# NuTubeAmp_1_0_1.net
KiCad netlist of a schematic drawn in EAGLE
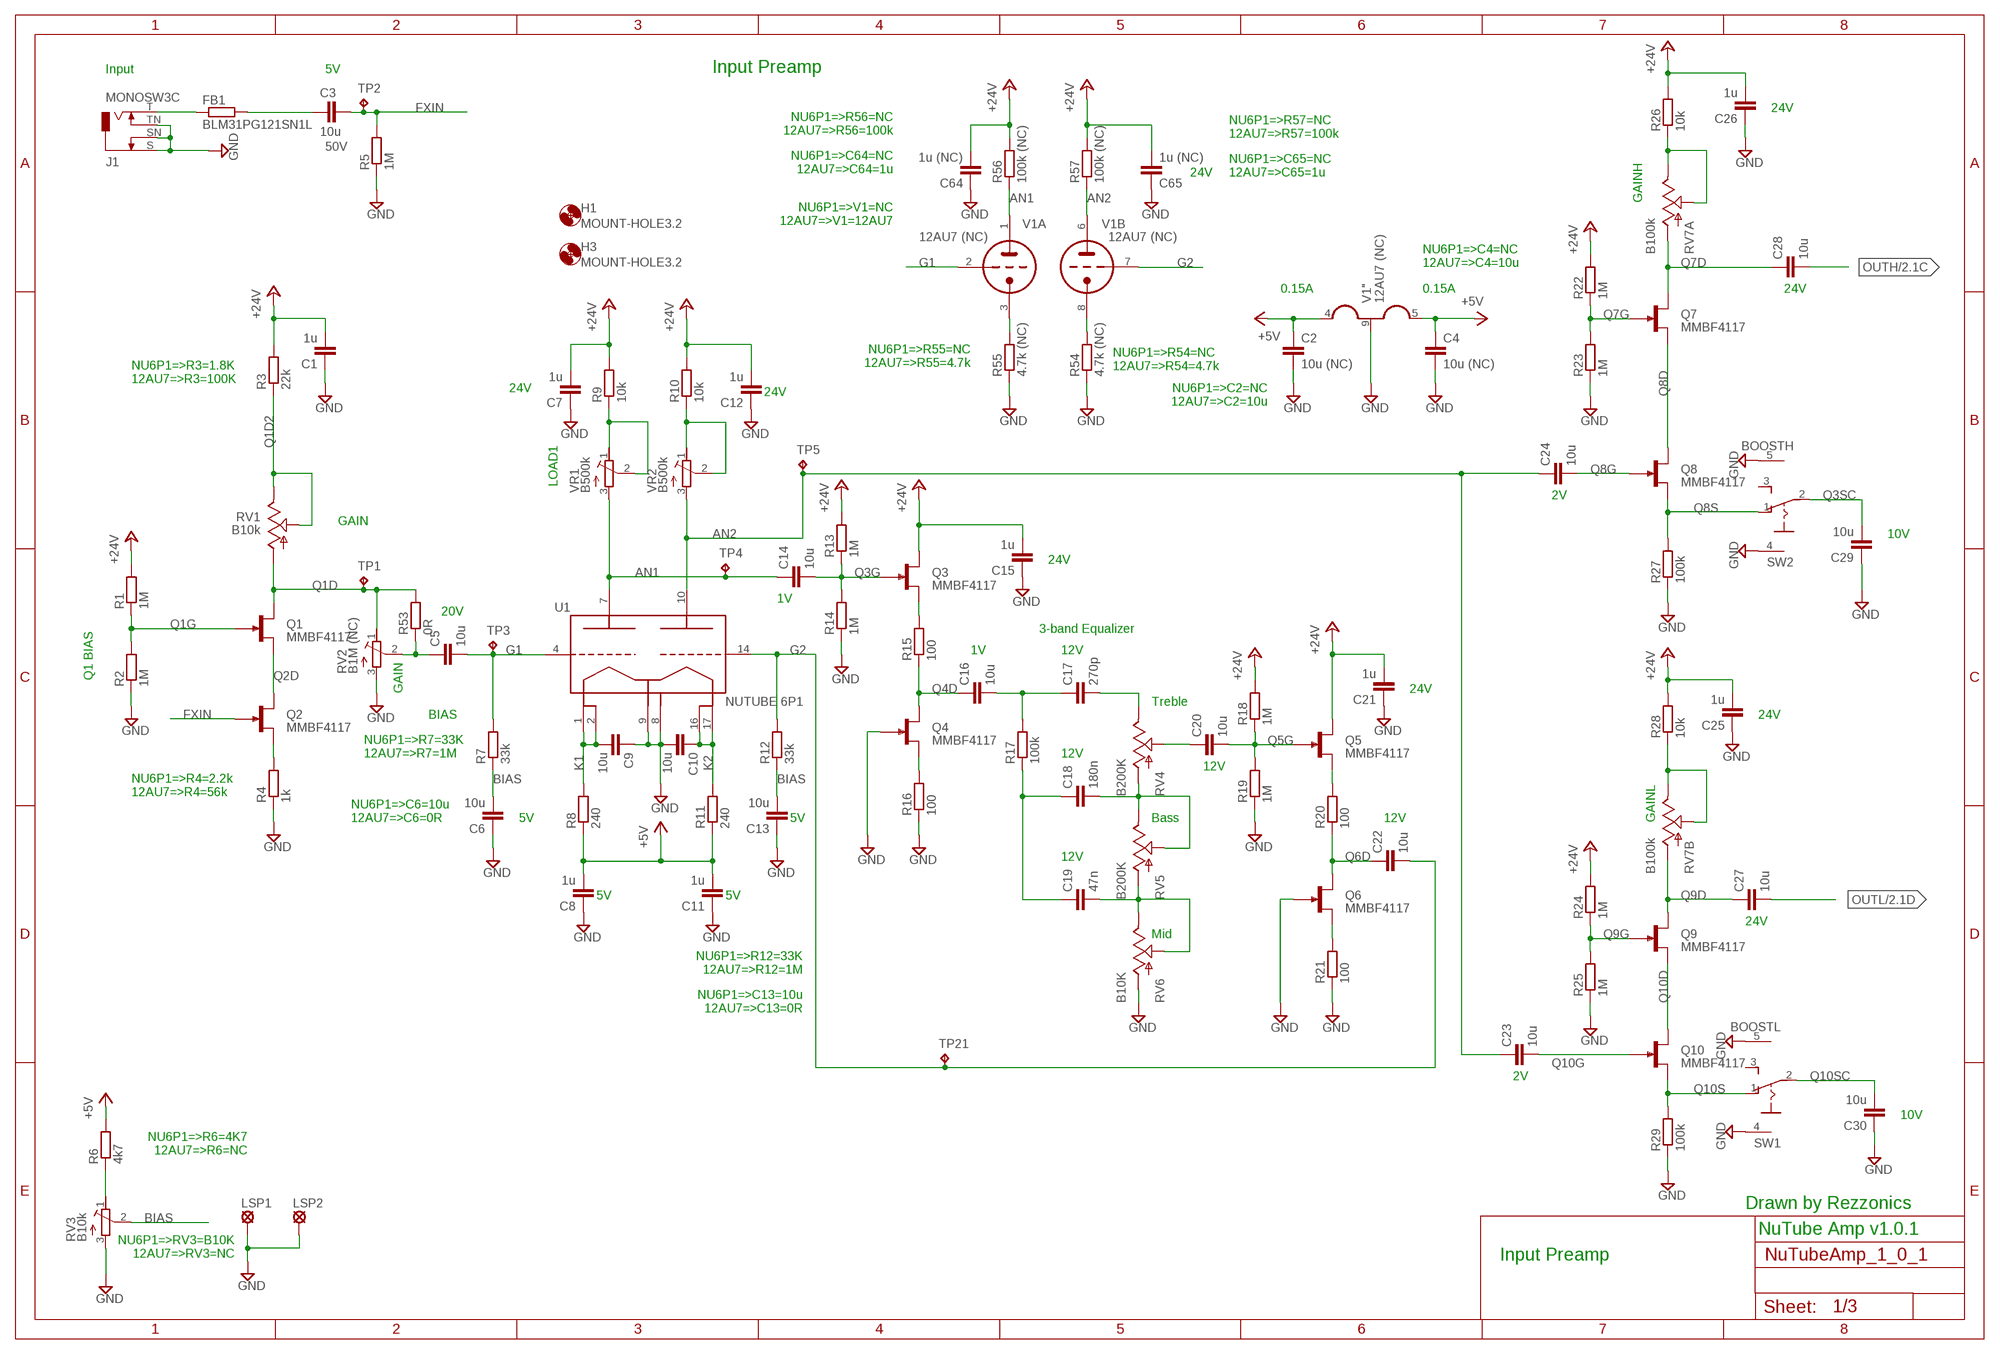
[diagram p0: schematic, sheet 1]
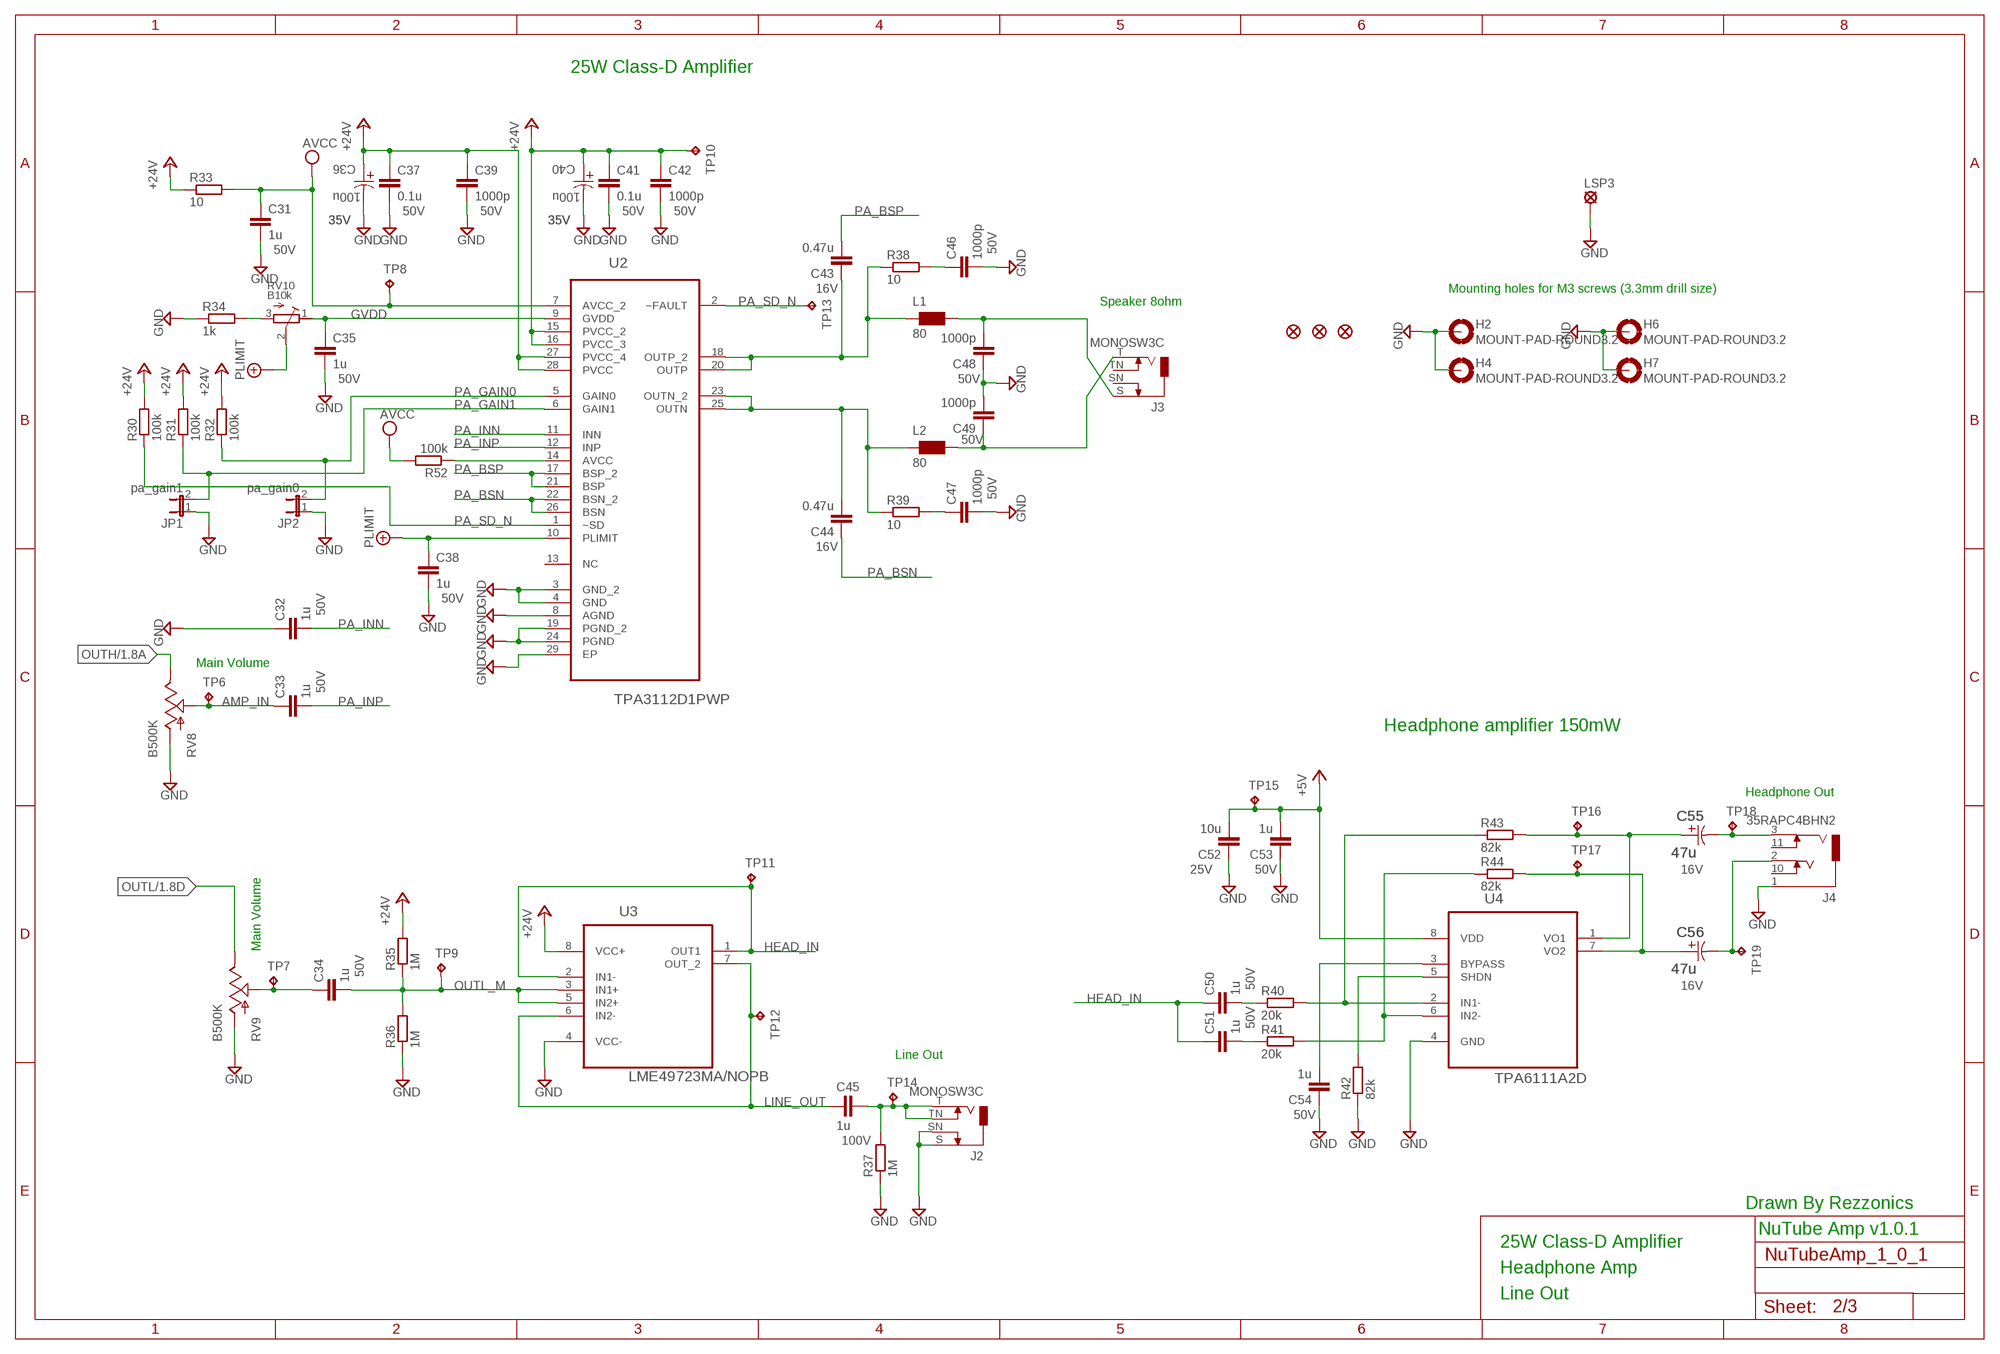
[diagram p1: schematic, sheet 2]
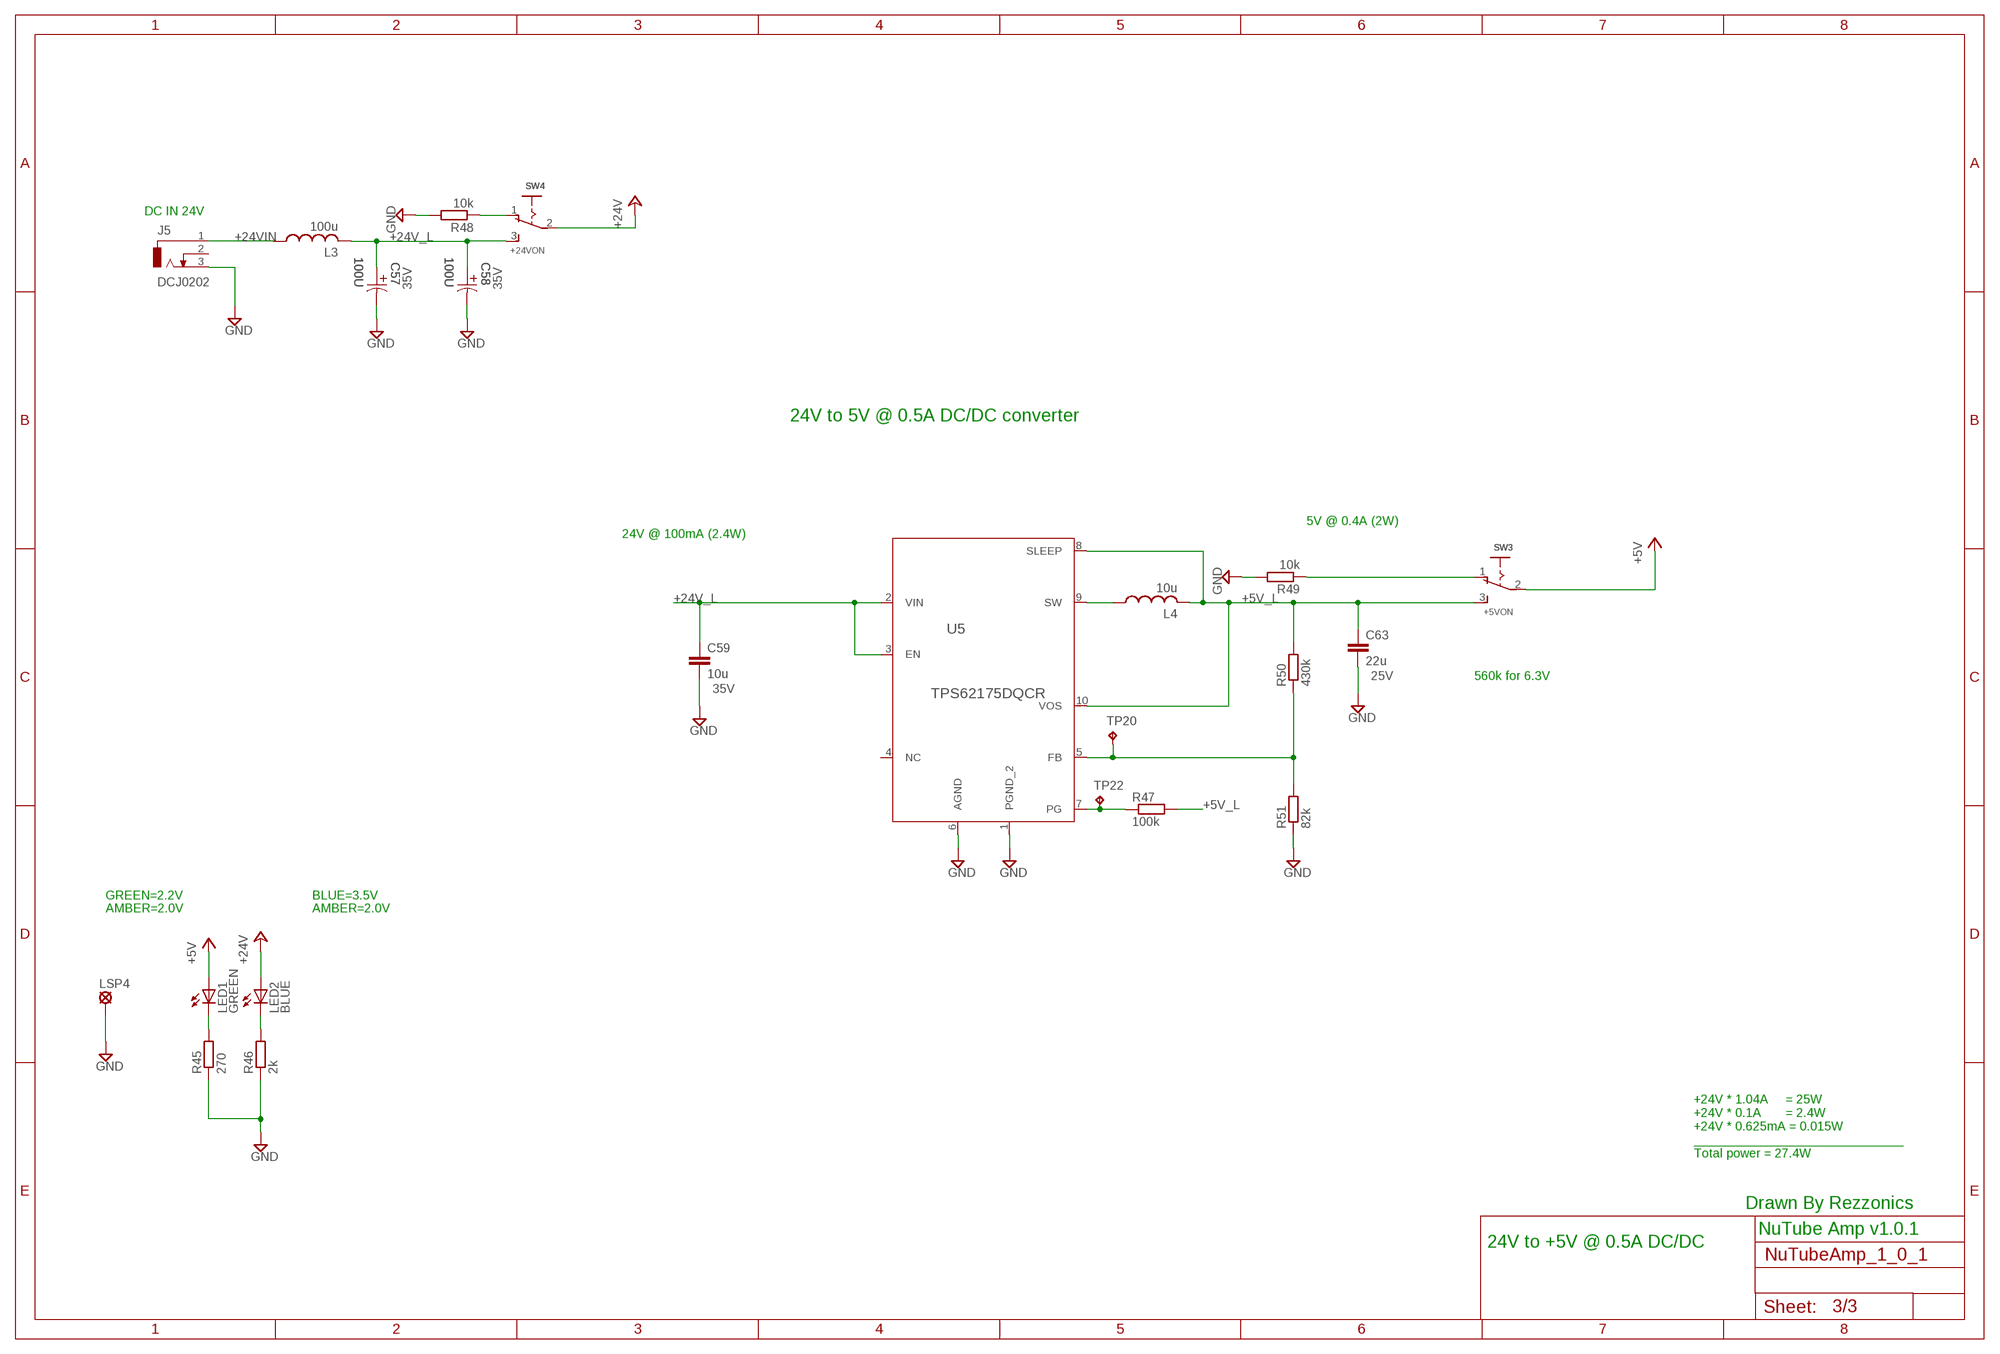
[diagram p2: schematic, sheet 3]

(export (version "E")
  (design (tool "Eeschema 10.0.6"))
  (components
    (comp (ref "C57")
      (value "100U")
      (footprint "eagle-import:CAPAE660X800N")
      (fields
        (field (name "MPN") "EEEHAV101XAP")
        (field (name "TOLERANCE") "±20 %")
        (field (name "VOLTAGERATING") "35V")
        (field (name "MPN_1") "EEE-1VA101XP")
        (field (name "VOLTAGERATING_1") "35V")
      )
      (libsource (lib "eagle-import") (part "EEE--CASE-D8HAV101XAP"))
    )
    (comp (ref "C58")
      (value "100U")
      (footprint "eagle-import:CAPAE660X800N")
      (fields
        (field (name "MPN") "EEEHAV101XAP")
        (field (name "TOLERANCE") "±20 %")
        (field (name "VOLTAGERATING") "35V")
        (field (name "MPN_1") "EEE-1VA101XP")
        (field (name "VOLTAGERATING_1") "35V")
      )
      (libsource (lib "eagle-import") (part "EEE--CASE-D8HAV101XAP"))
    )
    (comp (ref "C59")
      (value "10u")
      (footprint "eagle-import:C0805K")
      (fields (field (name "MPN") "GRM21BR6YA106KE43L") (field (name "VOLT") "35V"))
      (libsource (lib "eagle-import") (part "C-EUC0805K"))
    )
    (comp (ref "C63")
      (value "22u")
      (footprint "eagle-import:C0805K")
      (fields (field (name "MPN") "C2012X5R1V226M125AC") (field (name "VOLT") "25V"))
      (libsource (lib "eagle-import") (part "C-EUC0805K"))
    )
    (comp (ref "J5")
      (value "DCJ0202")
      (footprint "eagle-import:DCJ0202")
      (fields (field (name "MPN") "PJ-202A"))
      (libsource (lib "eagle-import") (part "DCJ0202"))
    )
    (comp (ref "L3")
      (value "100u")
      (footprint "eagle-import:SRN1060")
      (fields (field (name "MPN") "SRN1060-101M"))
      (libsource (lib "eagle-import") (part "SRN1060"))
    )
    (comp (ref "L4")
      (value "10u")
      (footprint "eagle-import:SRN4018")
      (fields (field (name "MPN") "SRN4018-100M"))
      (libsource (lib "eagle-import") (part "SRN4018"))
    )
    (comp (ref "LED1")
      (value "GREEN")
      (footprint "eagle-import:LED5MM")
      (fields (field (name "MPN") "SSL-LX5093GD"))
      (libsource (lib "eagle-import") (part "LED5MM"))
    )
    (comp (ref "LED2")
      (value "BLUE")
      (footprint "eagle-import:LED5MM")
      (fields (field (name "MPN") "SSL-LX5093USBD"))
      (libsource (lib "eagle-import") (part "LED5MM"))
    )
    (comp (ref "LSP4")
      (value "LSP13")
      (footprint "eagle-import:LSP13")
      (fields (field (name "MPN") "1249"))
      (libsource (lib "eagle-import") (part "LSP13"))
    )
    (comp (ref "R45")
      (value "270")
      (footprint "eagle-import:R0603")
      (fields (field (name "MPN") "ERJ-PA3F2700V"))
      (libsource (lib "eagle-import") (part "R-EU_R0603"))
    )
    (comp (ref "R46")
      (value "2k")
      (footprint "eagle-import:R0603")
      (fields (field (name "MPN") "ERJ-PA3F2001V"))
      (libsource (lib "eagle-import") (part "R-EU_R0603"))
    )
    (comp (ref "R47")
      (value "100k")
      (footprint "eagle-import:R0402")
      (fields (field (name "MPN") "ERJ-2RKF1003X"))
      (libsource (lib "eagle-import") (part "resistor_R-EU_R0402"))
    )
    (comp (ref "R48")
      (value "10k")
      (footprint "eagle-import:R0603")
      (fields (field (name "MPN") "CR0603-FX-1002HLF"))
      (libsource (lib "eagle-import") (part "R-EU_R0603"))
    )
    (comp (ref "R49")
      (value "10k")
      (footprint "eagle-import:R0603")
      (fields (field (name "MPN") "CR0603-FX-1002HLF"))
      (libsource (lib "eagle-import") (part "R-EU_R0603"))
    )
    (comp (ref "R50")
      (value "430k")
      (footprint "eagle-import:R0402")
      (fields (field (name "MPN") "ERJ-2GEJ434X"))
      (libsource (lib "eagle-import") (part "resistor_R-EU_R0402"))
    )
    (comp (ref "R51")
      (value "82k")
      (footprint "eagle-import:R0402")
      (fields (field (name "MPN") "ERJ-2RKF8202X"))
      (libsource (lib "eagle-import") (part "resistor_R-EU_R0402"))
    )
    (comp (ref "SW3")
      (value "+5VON")
      (footprint "eagle-import:GH39P0")
      (fields (field (name "MPN") "GH36P010001"))
      (libsource (lib "eagle-import") (part "SPDT1G"))
    )
    (comp (ref "SW4")
      (value "+24VON")
      (footprint "eagle-import:GH39P0")
      (fields (field (name "MPN") "GH36P010001"))
      (libsource (lib "eagle-import") (part "SPDT1G"))
    )
    (comp (ref "TP20")
      (value "TPTP10R")
      (footprint "eagle-import:TP10R")
      (libsource (lib "eagle-import") (part "TPTP10R"))
    )
    (comp (ref "TP22")
      (value "TPTP10R")
      (footprint "eagle-import:TP10R")
      (libsource (lib "eagle-import") (part "TPTP10R"))
    )
    (comp (ref "U5")
      (value "TPS62175DQCR")
      (footprint "eagle-import:R-PWSON-N10")
      (libsource (lib "eagle-import") (part "TPS62175DQCR"))
    )
    (comp (ref "C1")
      (value "1u")
      (footprint "eagle-import:C0603K")
      (fields (field (name "MPN") "C1608X5R1H105K080AB"))
      (libsource (lib "eagle-import") (part "C-EUC0603K"))
    )
    (comp (ref "C2")
      (value "10u (NC)")
      (footprint "eagle-import:C0805K")
      (fields (field (name "MPN") "GRM21BR6YA106KE43L"))
      (libsource (lib "eagle-import") (part "C-EUC0805K"))
    )
    (comp (ref "C3")
      (value "10u")
      (footprint "eagle-import:C0805K")
      (fields (field (name "MPN") "GRM21BR6YA106KE43L") (field (name "VOLT") "50V"))
      (libsource (lib "eagle-import") (part "C-EUC0805K"))
    )
    (comp (ref "C4")
      (value "10u (NC)")
      (footprint "eagle-import:C0805K")
      (fields (field (name "MPN") "GRM21BR6YA106KE43L"))
      (libsource (lib "eagle-import") (part "C-EUC0805K"))
    )
    (comp (ref "C5")
      (value "10u")
      (footprint "eagle-import:C0805K")
      (fields (field (name "MPN") "GRM21BR6YA106KE43L"))
      (libsource (lib "eagle-import") (part "C-EUC0805K"))
    )
    (comp (ref "C6")
      (value "10u")
      (footprint "eagle-import:C0805K")
      (fields (field (name "MPN") "GRM21BR6YA106KE43L"))
      (libsource (lib "eagle-import") (part "C-EUC0805K"))
    )
    (comp (ref "C7")
      (value "1u")
      (footprint "eagle-import:C0603K")
      (fields (field (name "MPN") "C1608X5R1H105K080AB"))
      (libsource (lib "eagle-import") (part "C-EUC0603K"))
    )
    (comp (ref "C8")
      (value "1u")
      (footprint "eagle-import:C0603K")
      (fields (field (name "MPN") "C1608X5R1H105K080AB"))
      (libsource (lib "eagle-import") (part "C-EUC0603K"))
    )
    (comp (ref "C9")
      (value "10u")
      (footprint "eagle-import:C0805K")
      (fields (field (name "MPN") "GRM21BR6YA106KE43L"))
      (libsource (lib "eagle-import") (part "C-EUC0805K"))
    )
    (comp (ref "C10")
      (value "10u")
      (footprint "eagle-import:C0805K")
      (fields (field (name "MPN") "GRM21BR6YA106KE43L"))
      (libsource (lib "eagle-import") (part "C-EUC0805K"))
    )
    (comp (ref "C11")
      (value "1u")
      (footprint "eagle-import:C0603K")
      (fields (field (name "MPN") "C1608X5R1H105K080AB"))
      (libsource (lib "eagle-import") (part "C-EUC0603K"))
    )
    (comp (ref "C12")
      (value "1u")
      (footprint "eagle-import:C0603K")
      (fields (field (name "MPN") "C1608X5R1H105K080AB"))
      (libsource (lib "eagle-import") (part "C-EUC0603K"))
    )
    (comp (ref "C13")
      (value "10u")
      (footprint "eagle-import:C0805K")
      (fields (field (name "MPN") "GRM21BR6YA106KE43L"))
      (libsource (lib "eagle-import") (part "C-EUC0805K"))
    )
    (comp (ref "C14")
      (value "10u")
      (footprint "eagle-import:C0805K")
      (fields (field (name "MPN") "GRM21BR6YA106KE43L"))
      (libsource (lib "eagle-import") (part "C-EUC0805K"))
    )
    (comp (ref "C15")
      (value "1u")
      (footprint "eagle-import:C0603K")
      (fields (field (name "MPN") "C1608X5R1H105K080AB"))
      (libsource (lib "eagle-import") (part "C-EUC0603K"))
    )
    (comp (ref "C16")
      (value "10u")
      (footprint "eagle-import:C0805K")
      (fields (field (name "MPN") "GRM21BR6YA106KE43L"))
      (libsource (lib "eagle-import") (part "C-EUC0805K"))
    )
    (comp (ref "C17")
      (value "270p")
      (footprint "eagle-import:C0402K")
      (fields (field (name "MPN") "GRM1555C1H271JA01D") (field (name "VOLT") "50V"))
      (libsource (lib "eagle-import") (part "C-EUC0402K"))
    )
    (comp (ref "C18")
      (value "180n")
      (footprint "eagle-import:C0603K")
      (fields (field (name "MPN") "GRM188R71C184KA01D") (field (name "VOLT") "16V"))
      (libsource (lib "eagle-import") (part "C-EUC0603K"))
    )
    (comp (ref "C19")
      (value "47n")
      (footprint "eagle-import:C0402K")
      (fields (field (name "MPN") "GRM155R71H473KE14D") (field (name "VOLT") "16V"))
      (libsource (lib "eagle-import") (part "C-EUC0402K"))
    )
    (comp (ref "C20")
      (value "10u")
      (footprint "eagle-import:C0805K")
      (fields (field (name "MPN") "GRM21BR6YA106KE43L"))
      (libsource (lib "eagle-import") (part "C-EUC0805K"))
    )
    (comp (ref "C21")
      (value "1u")
      (footprint "eagle-import:C0603K")
      (fields (field (name "MPN") "C1608X5R1H105K080AB"))
      (libsource (lib "eagle-import") (part "C-EUC0603K"))
    )
    (comp (ref "C22")
      (value "10u")
      (footprint "eagle-import:C0805K")
      (fields (field (name "MPN") "GRM21BR6YA106KE43L"))
      (libsource (lib "eagle-import") (part "C-EUC0805K"))
    )
    (comp (ref "C23")
      (value "10u")
      (footprint "eagle-import:C0805K")
      (fields (field (name "MPN") "GRM21BR6YA106KE43L"))
      (libsource (lib "eagle-import") (part "C-EUC0805K"))
    )
    (comp (ref "C24")
      (value "10u")
      (footprint "eagle-import:C0805K")
      (fields (field (name "MPN") "GRM21BR6YA106KE43L"))
      (libsource (lib "eagle-import") (part "C-EUC0805K"))
    )
    (comp (ref "C25")
      (value "1u")
      (footprint "eagle-import:C0603K")
      (fields (field (name "MPN") "C1608X5R1H105K080AB"))
      (libsource (lib "eagle-import") (part "C-EUC0603K"))
    )
    (comp (ref "C26")
      (value "1u")
      (footprint "eagle-import:C0603K")
      (fields (field (name "MPN") "C1608X5R1H105K080AB"))
      (libsource (lib "eagle-import") (part "C-EUC0603K"))
    )
    (comp (ref "C27")
      (value "10u")
      (footprint "eagle-import:C0805K")
      (fields (field (name "MPN") "GRM21BR6YA106KE43L"))
      (libsource (lib "eagle-import") (part "C-EUC0805K"))
    )
    (comp (ref "C28")
      (value "10u")
      (footprint "eagle-import:C0805K")
      (fields (field (name "MPN") "GRM21BR6YA106KE43L"))
      (libsource (lib "eagle-import") (part "C-EUC0805K"))
    )
    (comp (ref "C29")
      (value "10u")
      (footprint "eagle-import:C0805K")
      (fields (field (name "MPN") "GRM21BR6YA106KE43L"))
      (libsource (lib "eagle-import") (part "C-EUC0805K"))
    )
    (comp (ref "C30")
      (value "10u")
      (footprint "eagle-import:C0805K")
      (fields (field (name "MPN") "GRM21BR6YA106KE43L"))
      (libsource (lib "eagle-import") (part "C-EUC0805K"))
    )
    (comp (ref "C64")
      (value "1u (NC)")
      (footprint "eagle-import:C0603K")
      (fields (field (name "MPN") "C1608X5R1H105K080AB"))
      (libsource (lib "eagle-import") (part "C-EUC0603K"))
    )
    (comp (ref "C65")
      (value "1u (NC)")
      (footprint "eagle-import:C0603K")
      (fields (field (name "MPN") "C1608X5R1H105K080AB"))
      (libsource (lib "eagle-import") (part "C-EUC0603K"))
    )
    (comp (ref "FB1")
      (value "BLM31PG121SN1L")
      (footprint "eagle-import:R1206")
      (libsource (lib "eagle-import") (part "R-EU_R1206"))
    )
    (comp (ref "H1")
      (value "MOUNT-HOLE3.2")
      (footprint "eagle-import:3,2")
      (libsource (lib "eagle-import") (part "MOUNT-HOLE3.2"))
    )
    (comp (ref "H3")
      (value "MOUNT-HOLE3.2")
      (footprint "eagle-import:3,2")
      (libsource (lib "eagle-import") (part "MOUNT-HOLE3.2"))
    )
    (comp (ref "J1")
      (value "MONOSW3C")
      (footprint "eagle-import:NEUTRIK-NMJ4HCD2")
      (fields (field (name "MPN") "NMJ4HCD2"))
      (libsource (lib "eagle-import") (part "MONOSW3C"))
    )
    (comp (ref "LSP1")
      (value "LSP13")
      (footprint "eagle-import:LSP13")
      (fields (field (name "MPN") "1249"))
      (libsource (lib "eagle-import") (part "LSP13"))
    )
    (comp (ref "LSP2")
      (value "LSP13")
      (footprint "eagle-import:LSP13")
      (fields (field (name "MPN") "1249"))
      (libsource (lib "eagle-import") (part "LSP13"))
    )
    (comp (ref "Q1")
      (value "MMBF4117")
      (footprint "eagle-import:SOT23")
      (libsource (lib "eagle-import") (part "MMBF4117SOT23"))
    )
    (comp (ref "Q2")
      (value "MMBF4117")
      (footprint "eagle-import:SOT23")
      (libsource (lib "eagle-import") (part "MMBF4117SOT23"))
    )
    (comp (ref "Q3")
      (value "MMBF4117")
      (footprint "eagle-import:SOT23")
      (libsource (lib "eagle-import") (part "MMBF4117SOT23"))
    )
    (comp (ref "Q4")
      (value "MMBF4117")
      (footprint "eagle-import:SOT23")
      (libsource (lib "eagle-import") (part "MMBF4117SOT23"))
    )
    (comp (ref "Q5")
      (value "MMBF4117")
      (footprint "eagle-import:SOT23")
      (libsource (lib "eagle-import") (part "MMBF4117SOT23"))
    )
    (comp (ref "Q6")
      (value "MMBF4117")
      (footprint "eagle-import:SOT23")
      (libsource (lib "eagle-import") (part "MMBF4117SOT23"))
    )
    (comp (ref "Q7")
      (value "MMBF4117")
      (footprint "eagle-import:SOT23")
      (libsource (lib "eagle-import") (part "MMBF4117SOT23"))
    )
    (comp (ref "Q8")
      (value "MMBF4117")
      (footprint "eagle-import:SOT23")
      (libsource (lib "eagle-import") (part "MMBF4117SOT23"))
    )
    (comp (ref "Q9")
      (value "MMBF4117")
      (footprint "eagle-import:SOT23")
      (libsource (lib "eagle-import") (part "MMBF4117SOT23"))
    )
    (comp (ref "Q10")
      (value "MMBF4117")
      (footprint "eagle-import:SOT23")
      (libsource (lib "eagle-import") (part "MMBF4117SOT23"))
    )
    (comp (ref "R1")
      (value "1M")
      (footprint "eagle-import:R0402")
      (fields (field (name "MPN") "ERJ-2RKF1004X"))
      (libsource (lib "eagle-import") (part "resistor_R-EU_R0402"))
    )
    (comp (ref "R2")
      (value "1M")
      (footprint "eagle-import:R0402")
      (fields (field (name "MPN") "ERJ-2RKF1004X"))
      (libsource (lib "eagle-import") (part "resistor_R-EU_R0402"))
    )
    (comp (ref "R3")
      (value "22k")
      (footprint "eagle-import:R0402")
      (fields (field (name "MPN") "ERJ-2RKF1801X"))
      (libsource (lib "eagle-import") (part "resistor_R-EU_R0402"))
    )
    (comp (ref "R4")
      (value "1k")
      (footprint "eagle-import:R0402")
      (fields (field (name "MPN") "ERJ-2RKF2201X"))
      (libsource (lib "eagle-import") (part "resistor_R-EU_R0402"))
    )
    (comp (ref "R5")
      (value "1M")
      (footprint "eagle-import:R0402")
      (fields (field (name "MPN") "ERJ-2RKF1004X"))
      (libsource (lib "eagle-import") (part "resistor_R-EU_R0402"))
    )
    (comp (ref "R6")
      (value "4k7")
      (footprint "eagle-import:R0402")
      (fields (field (name "MPN") "ERJ-2RKF4701X"))
      (libsource (lib "eagle-import") (part "resistor_R-EU_R0402"))
    )
    (comp (ref "R7")
      (value "33k")
      (footprint "eagle-import:R0402")
      (fields (field (name "MPN") "ERJ-2RKF3302X"))
      (libsource (lib "eagle-import") (part "resistor_R-EU_R0402"))
    )
    (comp (ref "R8")
      (value "240")
      (footprint "eagle-import:R0603")
      (fields (field (name "MPN") "ERJ-3EKF2400V"))
      (libsource (lib "eagle-import") (part "R-EU_R0603"))
    )
    (comp (ref "R9")
      (value "10k")
      (footprint "eagle-import:R0402")
      (fields (field (name "MPN") "ERJ-2RKF1002X"))
      (libsource (lib "eagle-import") (part "resistor_R-EU_R0402"))
    )
    (comp (ref "R10")
      (value "10k")
      (footprint "eagle-import:R0402")
      (fields (field (name "MPN") "ERJ-2RKF1002X"))
      (libsource (lib "eagle-import") (part "resistor_R-EU_R0402"))
    )
    (comp (ref "R11")
      (value "240")
      (footprint "eagle-import:R0603")
      (fields (field (name "MPN") "ERJ-3EKF2400V"))
      (libsource (lib "eagle-import") (part "R-EU_R0603"))
    )
    (comp (ref "R12")
      (value "33k")
      (footprint "eagle-import:R0402")
      (fields (field (name "MPN") "ERJ-2RKF3302X"))
      (libsource (lib "eagle-import") (part "resistor_R-EU_R0402"))
    )
    (comp (ref "R13")
      (value "1M")
      (footprint "eagle-import:R0402")
      (fields (field (name "MPN") "ERJ-2RKF1004X"))
      (libsource (lib "eagle-import") (part "resistor_R-EU_R0402"))
    )
    (comp (ref "R14")
      (value "1M")
      (footprint "eagle-import:R0402")
      (fields (field (name "MPN") "ERJ-2RKF1004X"))
      (libsource (lib "eagle-import") (part "resistor_R-EU_R0402"))
    )
    (comp (ref "R15")
      (value "100")
      (footprint "eagle-import:R0402")
      (fields (field (name "MPN") "ERJ-2RKF1000X"))
      (libsource (lib "eagle-import") (part "resistor_R-EU_R0402"))
    )
    (comp (ref "R16")
      (value "100")
      (footprint "eagle-import:R0402")
      (fields (field (name "MPN") "ERJ-2RKF1000X"))
      (libsource (lib "eagle-import") (part "resistor_R-EU_R0402"))
    )
    (comp (ref "R17")
      (value "100k")
      (footprint "eagle-import:R0402")
      (fields (field (name "MPN") "ERJ-2RKF1003X"))
      (libsource (lib "eagle-import") (part "resistor_R-EU_R0402"))
    )
    (comp (ref "R18")
      (value "1M")
      (footprint "eagle-import:R0402")
      (fields (field (name "MPN") "ERJ-2RKF1004X"))
      (libsource (lib "eagle-import") (part "resistor_R-EU_R0402"))
    )
    (comp (ref "R19")
      (value "1M")
      (footprint "eagle-import:R0402")
      (fields (field (name "MPN") "ERJ-2RKF1004X"))
      (libsource (lib "eagle-import") (part "resistor_R-EU_R0402"))
    )
    (comp (ref "R20")
      (value "100")
      (footprint "eagle-import:R0402")
      (fields (field (name "MPN") "ERJ-2RKF1000X"))
      (libsource (lib "eagle-import") (part "resistor_R-EU_R0402"))
    )
    (comp (ref "R21")
      (value "100")
      (footprint "eagle-import:R0402")
      (fields (field (name "MPN") "ERJ-2RKF1000X"))
      (libsource (lib "eagle-import") (part "resistor_R-EU_R0402"))
    )
    (comp (ref "R22")
      (value "1M")
      (footprint "eagle-import:R0402")
      (fields (field (name "MPN") "ERJ-2RKF1004X"))
      (libsource (lib "eagle-import") (part "resistor_R-EU_R0402"))
    )
    (comp (ref "R23")
      (value "1M")
      (footprint "eagle-import:R0402")
      (fields (field (name "MPN") "ERJ-2RKF1004X"))
      (libsource (lib "eagle-import") (part "resistor_R-EU_R0402"))
    )
    (comp (ref "R24")
      (value "1M")
      (footprint "eagle-import:R0402")
      (fields (field (name "MPN") "ERJ-2RKF1004X"))
      (libsource (lib "eagle-import") (part "resistor_R-EU_R0402"))
    )
    (comp (ref "R25")
      (value "1M")
      (footprint "eagle-import:R0402")
      (fields (field (name "MPN") "ERJ-2RKF1004X"))
      (libsource (lib "eagle-import") (part "resistor_R-EU_R0402"))
    )
    (comp (ref "R26")
      (value "10k")
      (footprint "eagle-import:R0402")
      (fields (field (name "MPN") "ERJ-2RKF1002X"))
      (libsource (lib "eagle-import") (part "resistor_R-EU_R0402"))
    )
    (comp (ref "R27")
      (value "100k")
      (footprint "eagle-import:R0402")
      (fields (field (name "MPN") "ERJ-2RKF1003X"))
      (libsource (lib "eagle-import") (part "resistor_R-EU_R0402"))
    )
    (comp (ref "R28")
      (value "10k")
      (footprint "eagle-import:R0402")
      (fields (field (name "MPN") "ERJ-2RKF1002X"))
      (libsource (lib "eagle-import") (part "resistor_R-EU_R0402"))
    )
    (comp (ref "R29")
      (value "100k")
      (footprint "eagle-import:R0402")
      (fields (field (name "MPN") "ERJ-2RKF1003X"))
      (libsource (lib "eagle-import") (part "resistor_R-EU_R0402"))
    )
    (comp (ref "R53")
      (value "0R")
      (footprint "eagle-import:R0402")
      (fields (field (name "MPN") "ERJ-2GE0R00X"))
      (libsource (lib "eagle-import") (part "resistor_R-EU_R0402"))
    )
    (comp (ref "R54")
      (value "4.7k (NC)")
      (footprint "eagle-import:R0402")
      (fields (field (name "MPN") "ERJ-2RKF4701X"))
      (libsource (lib "eagle-import") (part "resistor_R-EU_R0402"))
    )
    (comp (ref "R55")
      (value "4.7k (NC)")
      (footprint "eagle-import:R0402")
      (fields (field (name "MPN") "ERJ-2RKF4701X"))
      (libsource (lib "eagle-import") (part "resistor_R-EU_R0402"))
    )
    (comp (ref "R56")
      (value "100k (NC)")
      (footprint "eagle-import:R0402")
      (fields (field (name "MPN") "ERJ-2RKF1003X"))
      (libsource (lib "eagle-import") (part "resistor_R-EU_R0402"))
    )
    (comp (ref "R57")
      (value "100k (NC)")
      (footprint "eagle-import:R0402")
      (fields (field (name "MPN") "ERJ-2RKF1003X"))
      (libsource (lib "eagle-import") (part "resistor_R-EU_R0402"))
    )
    (comp (ref "RV1")
      (value "B10k")
      (footprint "eagle-import:3310Y")
      (fields (field (name "MPN") "3310Y-001-103L"))
      (libsource (lib "eagle-import") (part "POT3310Y"))
    )
    (comp (ref "RV2")
      (value "B1M (NC)")
      (footprint "eagle-import:RTRIM3314G")
      (fields (field (name "MPN") "3314G-1-105E"))
      (libsource (lib "eagle-import") (part "R-TRIMM3314G"))
    )
    (comp (ref "RV3")
      (value "B10k")
      (footprint "eagle-import:RTRIM3314G")
      (fields (field (name "MPN") "3314G-2-103E"))
      (libsource (lib "eagle-import") (part "R-TRIMM3314G"))
    )
    (comp (ref "RV4")
      (value "B200K")
      (footprint "eagle-import:3310Y")
      (fields (field (name "MPN") "3310Y-001-204L"))
      (libsource (lib "eagle-import") (part "POT3310Y"))
    )
    (comp (ref "RV5")
      (value "B200K")
      (footprint "eagle-import:3310Y")
      (fields (field (name "MPN") "3310Y-001-204L"))
      (libsource (lib "eagle-import") (part "POT3310Y"))
    )
    (comp (ref "RV6")
      (value "B10K")
      (footprint "eagle-import:3310Y")
      (fields (field (name "MPN") "3310Y-001-103L"))
      (libsource (lib "eagle-import") (part "POT3310Y"))
    )
    (comp (ref "RV7")
      (value "B100k")
      (footprint "eagle-import:3310H")
      (fields (field (name "MPN") "3310H-001-104L"))
      (libsource (lib "eagle-import") (part "DPOT1"))
    )
    (comp (ref "SW1")
      (value "BOOSTL")
      (footprint "eagle-import:MHS122K")
      (fields (field (name "MPN") "MHS122K"))
      (libsource (lib "eagle-import") (part "SPDT"))
    )
    (comp (ref "SW2")
      (value "BOOSTH")
      (footprint "eagle-import:MHS122K")
      (fields (field (name "MPN") "MHS122K"))
      (libsource (lib "eagle-import") (part "SPDT"))
    )
    (comp (ref "TP1")
      (value "TPTP10R")
      (footprint "eagle-import:TP10R")
      (libsource (lib "eagle-import") (part "TPTP10R"))
    )
    (comp (ref "TP2")
      (value "TPTP10R")
      (footprint "eagle-import:TP10R")
      (libsource (lib "eagle-import") (part "TPTP10R"))
    )
    (comp (ref "TP3")
      (value "TPTP10R")
      (footprint "eagle-import:TP10R")
      (libsource (lib "eagle-import") (part "TPTP10R"))
    )
    (comp (ref "TP4")
      (value "TPTP10R")
      (footprint "eagle-import:TP10R")
      (libsource (lib "eagle-import") (part "TPTP10R"))
    )
    (comp (ref "TP5")
      (value "TPTP10R")
      (footprint "eagle-import:TP10R")
      (libsource (lib "eagle-import") (part "TPTP10R"))
    )
    (comp (ref "TP21")
      (value "TPTP10R")
      (footprint "eagle-import:TP10R")
      (libsource (lib "eagle-import") (part "TPTP10R"))
    )
    (comp (ref "U1")
      (value "NUTUBE 6P1")
      (footprint "eagle-import:NUTUBE_6P1_1")
      (libsource (lib "eagle-import") (part "NUTUBE_6P1_1"))
    )
    (comp (ref "V1")
      (value "12AU7 (NC)")
      (footprint "eagle-import:VT9")
      (fields (field (name "MPN") "*"))
      (libsource (lib "eagle-import") (part "12AU7-PVT9"))
    )
    (comp (ref "VR1")
      (value "B500k")
      (footprint "eagle-import:RTRIM3314G")
      (fields (field (name "MPN") "3314G-1-504E"))
      (libsource (lib "eagle-import") (part "R-TRIMM3314G"))
    )
    (comp (ref "VR2")
      (value "B500k")
      (footprint "eagle-import:RTRIM3314G")
      (fields (field (name "MPN") "3314G-1-504E"))
      (libsource (lib "eagle-import") (part "R-TRIMM3314G"))
    )
    (comp (ref "C31")
      (value "1u")
      (footprint "eagle-import:C0603K")
      (fields (field (name "MPN") "C1608X5R1H105K080AB") (field (name "VOLT") "50V"))
      (libsource (lib "eagle-import") (part "C-EUC0603K"))
    )
    (comp (ref "C32")
      (value "1u")
      (footprint "eagle-import:C0603K")
      (fields (field (name "MPN") "C1608X5R1H105K080AB") (field (name "VOLT") "50V"))
      (libsource (lib "eagle-import") (part "C-EUC0603K"))
    )
    (comp (ref "C33")
      (value "1u")
      (footprint "eagle-import:C0603K")
      (fields (field (name "MPN") "C1608X5R1H105K080AB") (field (name "VOLT") "50V"))
      (libsource (lib "eagle-import") (part "C-EUC0603K"))
    )
    (comp (ref "C34")
      (value "1u")
      (footprint "eagle-import:C0603K")
      (fields (field (name "MPN") "C1608X5R1H105K080AB") (field (name "VOLT") "50V"))
      (libsource (lib "eagle-import") (part "C-EUC0603K"))
    )
    (comp (ref "C35")
      (value "1u")
      (footprint "eagle-import:C0603K")
      (fields (field (name "MPN") "C1608X5R1H105K080AB") (field (name "VOLT") "50V"))
      (libsource (lib "eagle-import") (part "C-EUC0603K"))
    )
    (comp (ref "C36")
      (value "100u")
      (footprint "eagle-import:CAPAE660X800N")
      (fields
        (field (name "MPN") "EEEHAE101XAP")
        (field (name "TOLERANCE") "±20 %")
        (field (name "VOLTAGERATING") "25V")
        (field (name "MPN_1") "EEE-1VA101XP")
        (field (name "VOLT") "35V")
        (field (name "VOLTAGERATING_1") "35V")
      )
      (libsource (lib "eagle-import") (part "EEE--CASE-D8HAE101XAP"))
    )
    (comp (ref "C37")
      (value "0.1u")
      (footprint "eagle-import:C0603K")
      (fields (field (name "MPN") "GRM188R71H104KA93D") (field (name "VOLT") "50V"))
      (libsource (lib "eagle-import") (part "C-EUC0603K"))
    )
    (comp (ref "C38")
      (value "1u")
      (footprint "eagle-import:C0603K")
      (fields (field (name "MPN") "C1608X5R1H105K080AB") (field (name "VOLT") "50V"))
      (libsource (lib "eagle-import") (part "C-EUC0603K"))
    )
    (comp (ref "C39")
      (value "1000p")
      (footprint "eagle-import:C0603K")
      (fields (field (name "MPN") "GRM1885C1H102FA01D") (field (name "VOLT") "50V"))
      (libsource (lib "eagle-import") (part "C-EUC0603K"))
    )
    (comp (ref "C40")
      (value "100u")
      (footprint "eagle-import:CAPAE660X800N")
      (fields
        (field (name "MPN") "EEEHAE101XAP")
        (field (name "TOLERANCE") "±20 %")
        (field (name "VOLTAGERATING") "25V")
        (field (name "MPN_1") "EEE-1VA101XP")
        (field (name "VOLT") "35V")
        (field (name "VOLTAGERATING_1") "35V")
      )
      (libsource (lib "eagle-import") (part "EEE--CASE-D8HAE101XAP"))
    )
    (comp (ref "C41")
      (value "0.1u")
      (footprint "eagle-import:C0603K")
      (fields (field (name "MPN") "GRM188R71H104KA93D") (field (name "VOLT") "50V"))
      (libsource (lib "eagle-import") (part "C-EUC0603K"))
    )
    (comp (ref "C42")
      (value "1000p")
      (footprint "eagle-import:C0603K")
      (fields (field (name "MPN") "GRM1885C1H102FA01D") (field (name "VOLT") "50V"))
      (libsource (lib "eagle-import") (part "C-EUC0603K"))
    )
    (comp (ref "C43")
      (value "0.47u")
      (footprint "eagle-import:C0603K")
      (fields (field (name "MPN") "GRM188R71C474KA88D") (field (name "VOLT") "16V"))
      (libsource (lib "eagle-import") (part "C-EUC0603K"))
    )
    (comp (ref "C44")
      (value "0.47u")
      (footprint "eagle-import:C0603K")
      (fields (field (name "MPN") "GRM188R71C474KA88D") (field (name "VOLT") "16V"))
      (libsource (lib "eagle-import") (part "C-EUC0603K"))
    )
    (comp (ref "C45")
      (value "1u")
      (footprint "eagle-import:C0603K")
      (fields (field (name "MPN") "C1608X5R1H105K080AB") (field (name "VOLT") "100V"))
      (libsource (lib "eagle-import") (part "C-EUC0603K"))
    )
    (comp (ref "C46")
      (value "1000p")
      (footprint "eagle-import:C0603K")
      (fields (field (name "MPN") "GRM1885C1H102FA01D") (field (name "VOLT") "50V"))
      (libsource (lib "eagle-import") (part "C-EUC0603K"))
    )
    (comp (ref "C47")
      (value "1000p")
      (footprint "eagle-import:C0603K")
      (fields (field (name "MPN") "GRM1885C1H102FA01D") (field (name "VOLT") "50V"))
      (libsource (lib "eagle-import") (part "C-EUC0603K"))
    )
    (comp (ref "C48")
      (value "1000p")
      (footprint "eagle-import:C0603K")
      (fields (field (name "MPN") "GRM1885C1H102FA01D") (field (name "VOLT") "50V"))
      (libsource (lib "eagle-import") (part "C-EUC0603K"))
    )
    (comp (ref "C49")
      (value "1000p")
      (footprint "eagle-import:C0603K")
      (fields (field (name "MPN") "GRM1885C1H102FA01D") (field (name "VOLT") "50V"))
      (libsource (lib "eagle-import") (part "C-EUC0603K"))
    )
    (comp (ref "C50")
      (value "1u")
      (footprint "eagle-import:C0603K")
      (fields (field (name "MPN") "C1608X5R1H105K080AB") (field (name "VOLT") "50V"))
      (libsource (lib "eagle-import") (part "C-EUC0603K"))
    )
    (comp (ref "C51")
      (value "1u")
      (footprint "eagle-import:C0603K")
      (fields (field (name "MPN") "C1608X5R1H105K080AB") (field (name "VOLT") "50V"))
      (libsource (lib "eagle-import") (part "C-EUC0603K"))
    )
    (comp (ref "C52")
      (value "10u")
      (footprint "eagle-import:C0805K")
      (fields (field (name "MPN") "GRM21BR6YA106KE43L") (field (name "VOLT") "25V"))
      (libsource (lib "eagle-import") (part "C-EUC0805K"))
    )
    (comp (ref "C53")
      (value "1u")
      (footprint "eagle-import:C0603K")
      (fields (field (name "MPN") "C1608X5R1H105K080AB") (field (name "VOLT") "50V"))
      (libsource (lib "eagle-import") (part "C-EUC0603K"))
    )
    (comp (ref "C54")
      (value "1u")
      (footprint "eagle-import:C0603K")
      (fields (field (name "MPN") "C1608X5R1H105K080AB") (field (name "VOLT") "50V"))
      (libsource (lib "eagle-import") (part "C-EUC0603K"))
    )
    (comp (ref "C55")
      (value "47u")
      (footprint "eagle-import:CAPAE530X610N")
      (fields
        (field (name "MPN") "EEEHBC470UAR")
        (field (name "TOLERANCE") "±20 %")
        (field (name "MPN_1") "EEE-HBC470UAR")
        (field (name "VOLT") "16V")
      )
      (libsource (lib "eagle-import") (part "EEE--CASE-CHBC470UAR"))
    )
    (comp (ref "C56")
      (value "47u")
      (footprint "eagle-import:CAPAE530X610N")
      (fields
        (field (name "MPN") "EEEHBC470UAR")
        (field (name "TOLERANCE") "±20 %")
        (field (name "MPN_1") "EEE-HBC470UAR")
        (field (name "VOLT") "16V")
      )
      (libsource (lib "eagle-import") (part "EEE--CASE-CHBC470UAR"))
    )
    (comp (ref "H2")
      (value "MOUNT-PAD-ROUND3.2")
      (footprint "eagle-import:3,2-PAD")
      (libsource (lib "eagle-import") (part "MOUNT-PAD-ROUND3.2"))
    )
    (comp (ref "H4")
      (value "MOUNT-PAD-ROUND3.2")
      (footprint "eagle-import:3,2-PAD")
      (libsource (lib "eagle-import") (part "MOUNT-PAD-ROUND3.2"))
    )
    (comp (ref "H6")
      (value "MOUNT-PAD-ROUND3.2")
      (footprint "eagle-import:3,2-PAD")
      (libsource (lib "eagle-import") (part "MOUNT-PAD-ROUND3.2"))
    )
    (comp (ref "H7")
      (value "MOUNT-PAD-ROUND3.2")
      (footprint "eagle-import:3,2-PAD")
      (libsource (lib "eagle-import") (part "MOUNT-PAD-ROUND3.2"))
    )
    (comp (ref "J2")
      (value "MONOSW3C")
      (footprint "eagle-import:NEUTRIK-NMJ4HCD2")
      (fields (field (name "MPN") "NMJ4HCD2"))
      (libsource (lib "eagle-import") (part "MONOSW3C"))
    )
    (comp (ref "J3")
      (value "MONOSW3C")
      (footprint "eagle-import:NEUTRIK-NMJ4HCD2")
      (fields (field (name "MPN") "NMJ4HCD2"))
      (libsource (lib "eagle-import") (part "MONOSW3C"))
    )
    (comp (ref "J4")
      (value "35RAPC4BHN2")
      (footprint "eagle-import:35RAPC4BHN2")
      (libsource (lib "eagle-import") (part "35RAPC4BHN2"))
    )
    (comp (ref "JP1")
      (value "pa_gain1")
      (footprint "eagle-import:1X02")
      (fields (field (name "MPN") "77311-401-36LF"))
      (libsource (lib "eagle-import") (part "JUMPER-2PTH"))
    )
    (comp (ref "JP2")
      (value "pa_gain0")
      (footprint "eagle-import:1X02")
      (fields (field (name "MPN") "77311-401-36LF"))
      (libsource (lib "eagle-import") (part "JUMPER-2PTH"))
    )
    (comp (ref "JP3")
      (value "FIDUCIAL1X2.5")
      (footprint "eagle-import:FIDUCIAL-1X2.5")
      (libsource (lib "eagle-import") (part "FIDUCIAL1X2.5"))
    )
    (comp (ref "JP4")
      (value "FIDUCIAL1X2.5")
      (footprint "eagle-import:FIDUCIAL-1X2.5")
      (libsource (lib "eagle-import") (part "FIDUCIAL1X2.5"))
    )
    (comp (ref "JP5")
      (value "FIDUCIAL1X2.5")
      (footprint "eagle-import:FIDUCIAL-1X2.5")
      (libsource (lib "eagle-import") (part "FIDUCIAL1X2.5"))
    )
    (comp (ref "L1")
      (value "80")
      (footprint "eagle-import:0805")
      (fields (field (name "MPN") "HI0805R800R-10"))
      (libsource (lib "eagle-import") (part "WE-CBF_0805"))
    )
    (comp (ref "L2")
      (value "80")
      (footprint "eagle-import:0805")
      (fields (field (name "MPN") "HI0805R800R-10"))
      (libsource (lib "eagle-import") (part "WE-CBF_0805"))
    )
    (comp (ref "LSP3")
      (value "LSP13")
      (footprint "eagle-import:LSP13")
      (fields (field (name "MPN") "1249"))
      (libsource (lib "eagle-import") (part "LSP13"))
    )
    (comp (ref "R30")
      (value "100k")
      (footprint "eagle-import:R0603")
      (fields (field (name "MPN") "ERJ-3EKF1003V"))
      (libsource (lib "eagle-import") (part "R-EU_R0603"))
    )
    (comp (ref "R31")
      (value "100k")
      (footprint "eagle-import:R0603")
      (fields (field (name "MPN") "ERJ-3EKF1003V"))
      (libsource (lib "eagle-import") (part "R-EU_R0603"))
    )
    (comp (ref "R32")
      (value "100k")
      (footprint "eagle-import:R0603")
      (fields (field (name "MPN") "ERJ-3EKF1003V"))
      (libsource (lib "eagle-import") (part "R-EU_R0603"))
    )
    (comp (ref "R33")
      (value "10")
      (footprint "eagle-import:R0603")
      (fields (field (name "MPN") "CRCW060310R0FKEAHP"))
      (libsource (lib "eagle-import") (part "R-EU_R0603"))
    )
    (comp (ref "R34")
      (value "1k")
      (footprint "eagle-import:R0603")
      (fields (field (name "MPN") "ERJ-3EKF1001V"))
      (libsource (lib "eagle-import") (part "R-EU_R0603"))
    )
    (comp (ref "R35")
      (value "1M")
      (footprint "eagle-import:R0402")
      (fields (field (name "MPN") "ERJ-2RKF1004X"))
      (libsource (lib "eagle-import") (part "resistor_R-EU_R0402"))
    )
    (comp (ref "R36")
      (value "1M")
      (footprint "eagle-import:R0402")
      (fields (field (name "MPN") "ERJ-2RKF1004X"))
      (libsource (lib "eagle-import") (part "resistor_R-EU_R0402"))
    )
    (comp (ref "R37")
      (value "1M")
      (footprint "eagle-import:R0402")
      (fields (field (name "MPN") "ERJ-2RKF1004X"))
      (libsource (lib "eagle-import") (part "resistor_R-EU_R0402"))
    )
    (comp (ref "R38")
      (value "10")
      (footprint "eagle-import:R0603")
      (fields (field (name "MPN") "CRCW060310R0FKEAHP"))
      (libsource (lib "eagle-import") (part "R-EU_R0603"))
    )
    (comp (ref "R39")
      (value "10")
      (footprint "eagle-import:R0603")
      (fields (field (name "MPN") "CRCW060310R0FKEAHP"))
      (libsource (lib "eagle-import") (part "R-EU_R0603"))
    )
    (comp (ref "R40")
      (value "20k")
      (footprint "eagle-import:R0603")
      (fields (field (name "MPN") "ERJ-3EKF2002V"))
      (libsource (lib "eagle-import") (part "resistor_R-EU_R0603"))
    )
    (comp (ref "R41")
      (value "20k")
      (footprint "eagle-import:R0603")
      (fields (field (name "MPN") "ERJ-3EKF2002V"))
      (libsource (lib "eagle-import") (part "resistor_R-EU_R0603"))
    )
    (comp (ref "R42")
      (value "82k")
      (footprint "eagle-import:R0603")
      (fields (field (name "MPN") "ERJ-3EKF8202V"))
      (libsource (lib "eagle-import") (part "resistor_R-EU_R0603"))
    )
    (comp (ref "R43")
      (value "82k")
      (footprint "eagle-import:R0603")
      (fields (field (name "MPN") "ERJ-3EKF8202V"))
      (libsource (lib "eagle-import") (part "resistor_R-EU_R0603"))
    )
    (comp (ref "R44")
      (value "82k")
      (footprint "eagle-import:R0603")
      (fields (field (name "MPN") "ERJ-3EKF8202V"))
      (libsource (lib "eagle-import") (part "resistor_R-EU_R0603"))
    )
    (comp (ref "R52")
      (value "100k")
      (footprint "eagle-import:R0603")
      (fields (field (name "MPN") "ERJ-3EKF1003V"))
      (libsource (lib "eagle-import") (part "R-EU_R0603"))
    )
    (comp (ref "RV8")
      (value "B500K")
      (footprint "eagle-import:3310Y")
      (fields (field (name "MPN") "3310Y-001-504L"))
      (libsource (lib "eagle-import") (part "POT3310Y"))
    )
    (comp (ref "RV9")
      (value "B500K")
      (footprint "eagle-import:3310Y")
      (fields (field (name "MPN") "3310Y-001-504L"))
      (libsource (lib "eagle-import") (part "POT3310Y"))
    )
    (comp (ref "RV10")
      (value "B10k")
      (footprint "eagle-import:RTRIM3314G")
      (fields (field (name "MPN") "3314G-2-103E"))
      (libsource (lib "eagle-import") (part "R-TRIMM3314G"))
    )
    (comp (ref "TP6")
      (value "TPTP10R")
      (footprint "eagle-import:TP10R")
      (libsource (lib "eagle-import") (part "TPTP10R"))
    )
    (comp (ref "TP7")
      (value "TPTP10R")
      (footprint "eagle-import:TP10R")
      (libsource (lib "eagle-import") (part "TPTP10R"))
    )
    (comp (ref "TP8")
      (value "TPTP10R")
      (footprint "eagle-import:TP10R")
      (libsource (lib "eagle-import") (part "TPTP10R"))
    )
    (comp (ref "TP9")
      (value "TPTP10R")
      (footprint "eagle-import:TP10R")
      (libsource (lib "eagle-import") (part "TPTP10R"))
    )
    (comp (ref "TP10")
      (value "TPTP10R")
      (footprint "eagle-import:TP10R")
      (libsource (lib "eagle-import") (part "TPTP10R"))
    )
    (comp (ref "TP11")
      (value "TPTP10R")
      (footprint "eagle-import:TP10R")
      (libsource (lib "eagle-import") (part "TPTP10R"))
    )
    (comp (ref "TP12")
      (value "TPTP10R")
      (footprint "eagle-import:TP10R")
      (libsource (lib "eagle-import") (part "TPTP10R"))
    )
    (comp (ref "TP13")
      (value "TPTP10R")
      (footprint "eagle-import:TP10R")
      (libsource (lib "eagle-import") (part "TPTP10R"))
    )
    (comp (ref "TP14")
      (value "TPTP10R")
      (footprint "eagle-import:TP10R")
      (libsource (lib "eagle-import") (part "TPTP10R"))
    )
    (comp (ref "TP15")
      (value "TPTP10R")
      (footprint "eagle-import:TP10R")
      (libsource (lib "eagle-import") (part "TPTP10R"))
    )
    (comp (ref "TP16")
      (value "TPTP10R")
      (footprint "eagle-import:TP10R")
      (libsource (lib "eagle-import") (part "TPTP10R"))
    )
    (comp (ref "TP17")
      (value "TPTP10R")
      (footprint "eagle-import:TP10R")
      (libsource (lib "eagle-import") (part "TPTP10R"))
    )
    (comp (ref "TP18")
      (value "TPTP10R")
      (footprint "eagle-import:TP10R")
      (libsource (lib "eagle-import") (part "TPTP10R"))
    )
    (comp (ref "TP19")
      (value "TPTP10R")
      (footprint "eagle-import:TP10R")
      (libsource (lib "eagle-import") (part "TPTP10R"))
    )
    (comp (ref "U2")
      (value "TPA3112D1PWP")
      (footprint "eagle-import:SOP65P640X120-29N")
      (fields (field (name "MPN") "TPA3112D1PWP"))
      (libsource (lib "eagle-import") (part "TPA3112D1PWP"))
    )
    (comp (ref "U3")
      (value "LME49723MA/NOPB")
      (footprint "eagle-import:SOIC127P600X175-8N")
      (fields (field (name "MPN") "TL972ID") (field (name "MPN_1") "LME49723MA/NOPB"))
      (libsource (lib "eagle-import") (part "TL972ID"))
    )
    (comp (ref "U4")
      (value "TPA6111A2D")
      (footprint "eagle-import:SOIC127P600X175-8N")
      (fields (field (name "MPN") "TPA6111A2D"))
      (libsource (lib "eagle-import") (part "TPA6111A2D"))
    )
  )
  (nets
    (net (code "1") (name "+5V") (class "Default")
      (node (ref "C11") (pin "2") (pinfunction "2_2") (pintype "passive"))
      (node (ref "C2") (pin "1") (pinfunction "1_1") (pintype "passive"))
      (node (ref "C4") (pin "1") (pinfunction "1_1") (pintype "passive"))
      (node (ref "C52") (pin "2") (pinfunction "2_2") (pintype "passive"))
      (node (ref "C53") (pin "2") (pinfunction "2_2") (pintype "passive"))
      (node (ref "C8") (pin "2") (pinfunction "2_2") (pintype "passive"))
      (node (ref "LED1") (pin "A") (pinfunction "A_A") (pintype "passive"))
      (node (ref "R11") (pin "1") (pinfunction "1_1") (pintype "passive"))
      (node (ref "R6") (pin "2") (pinfunction "2_2") (pintype "passive"))
      (node (ref "R8") (pin "1") (pinfunction "1_1") (pintype "passive"))
      (node (ref "SW3") (pin "2") (pinfunction "P_2") (pintype "passive"))
      (node (ref "TP15") (pin "TP") (pinfunction "TP_TP") (pintype "input"))
      (node (ref "U4") (pin "8") (pinfunction "VDD_8") (pintype "power_in"))
      (node (ref "V1") (pin "4") (pinfunction "H1_4") (pintype "passive"))
      (node (ref "V1") (pin "5") (pinfunction "H3_5") (pintype "passive"))
    )
    (net (code "2") (name "+5V_L") (class "Default")
      (node (ref "C63") (pin "1") (pinfunction "1_1") (pintype "passive"))
      (node (ref "L4") (pin "2") (pinfunction "2_2") (pintype "passive"))
      (node (ref "R47") (pin "2") (pinfunction "2_2") (pintype "passive"))
      (node (ref "R50") (pin "2") (pinfunction "2_2") (pintype "passive"))
      (node (ref "SW3") (pin "3") (pinfunction "S_3") (pintype "passive"))
      (node (ref "U5") (pin "10") (pinfunction "VOS_10") (pintype "passive"))
      (node (ref "U5") (pin "8") (pinfunction "SLEEP_8") (pintype "passive"))
    )
    (net (code "3") (name "+24V") (class "Default")
      (node (ref "C1") (pin "2") (pinfunction "2_2") (pintype "passive"))
      (node (ref "C12") (pin "2") (pinfunction "2_2") (pintype "passive"))
      (node (ref "C15") (pin "2") (pinfunction "2_2") (pintype "passive"))
      (node (ref "C21") (pin "2") (pinfunction "2_2") (pintype "passive"))
      (node (ref "C25") (pin "2") (pinfunction "2_2") (pintype "passive"))
      (node (ref "C26") (pin "2") (pinfunction "2_2") (pintype "passive"))
      (node (ref "C36") (pin "1") (pinfunction "1_1") (pintype "passive"))
      (node (ref "C37") (pin "1") (pinfunction "1_1") (pintype "passive"))
      (node (ref "C39") (pin "1") (pinfunction "1_1") (pintype "passive"))
      (node (ref "C40") (pin "1") (pinfunction "1_1") (pintype "passive"))
      (node (ref "C41") (pin "1") (pinfunction "1_1") (pintype "passive"))
      (node (ref "C42") (pin "1") (pinfunction "1_1") (pintype "passive"))
      (node (ref "C64") (pin "2") (pinfunction "2_2") (pintype "passive"))
      (node (ref "C65") (pin "2") (pinfunction "2_2") (pintype "passive"))
      (node (ref "C7") (pin "2") (pinfunction "2_2") (pintype "passive"))
      (node (ref "LED2") (pin "A") (pinfunction "A_A") (pintype "passive"))
      (node (ref "Q3") (pin "1") (pinfunction "D_1") (pintype "passive"))
      (node (ref "Q5") (pin "1") (pinfunction "D_1") (pintype "passive"))
      (node (ref "R1") (pin "2") (pinfunction "2_2") (pintype "passive"))
      (node (ref "R10") (pin "2") (pinfunction "2_2") (pintype "passive"))
      (node (ref "R13") (pin "2") (pinfunction "2_2") (pintype "passive"))
      (node (ref "R18") (pin "2") (pinfunction "2_2") (pintype "passive"))
      (node (ref "R22") (pin "2") (pinfunction "2_2") (pintype "passive"))
      (node (ref "R24") (pin "2") (pinfunction "2_2") (pintype "passive"))
      (node (ref "R26") (pin "2") (pinfunction "2_2") (pintype "passive"))
      (node (ref "R28") (pin "2") (pinfunction "2_2") (pintype "passive"))
      (node (ref "R3") (pin "2") (pinfunction "2_2") (pintype "passive"))
      (node (ref "R30") (pin "2") (pinfunction "2_2") (pintype "passive"))
      (node (ref "R31") (pin "2") (pinfunction "2_2") (pintype "passive"))
      (node (ref "R32") (pin "2") (pinfunction "2_2") (pintype "passive"))
      (node (ref "R33") (pin "1") (pinfunction "1_1") (pintype "passive"))
      (node (ref "R35") (pin "2") (pinfunction "2_2") (pintype "passive"))
      (node (ref "R56") (pin "2") (pinfunction "2_2") (pintype "passive"))
      (node (ref "R57") (pin "2") (pinfunction "2_2") (pintype "passive"))
      (node (ref "R9") (pin "2") (pinfunction "2_2") (pintype "passive"))
      (node (ref "SW4") (pin "2") (pinfunction "P_2") (pintype "passive"))
      (node (ref "TP10") (pin "TP") (pinfunction "TP_TP") (pintype "input"))
      (node (ref "U2") (pin "15") (pinfunction "PVCC_2_15") (pintype "power_in"))
      (node (ref "U2") (pin "16") (pinfunction "PVCC_3_16") (pintype "power_in"))
      (node (ref "U2") (pin "27") (pinfunction "PVCC_4_27") (pintype "power_in"))
      (node (ref "U2") (pin "28") (pinfunction "PVCC_28") (pintype "power_in"))
      (node (ref "U3") (pin "8") (pinfunction "VCC+_8") (pintype "power_in"))
    )
    (net (code "4") (name "+24VIN") (class "Default")
      (node (ref "J5") (pin "1") (pinfunction "1_1") (pintype "passive"))
      (node (ref "L3") (pin "1") (pinfunction "1_1") (pintype "passive"))
    )
    (net (code "5") (name "+24V_L") (class "Default")
      (node (ref "C57") (pin "1") (pinfunction "1_1") (pintype "passive"))
      (node (ref "C58") (pin "1") (pinfunction "1_1") (pintype "passive"))
      (node (ref "C59") (pin "1") (pinfunction "1_1") (pintype "passive"))
      (node (ref "L3") (pin "2") (pinfunction "2_2") (pintype "passive"))
      (node (ref "SW4") (pin "3") (pinfunction "S_3") (pintype "passive"))
      (node (ref "U5") (pin "2") (pinfunction "VIN_2") (pintype "passive"))
      (node (ref "U5") (pin "3") (pinfunction "EN_3") (pintype "passive"))
    )
    (net (code "6") (name "+UB") (class "Default")
      (node (ref "C38") (pin "1") (pinfunction "1_1") (pintype "passive"))
      (node (ref "RV10") (pin "2") (pinfunction "S_2") (pintype "passive"))
      (node (ref "U2") (pin "10") (pinfunction "PLIMIT_10") (pintype "input"))
    )
    (net (code "7") (name "AMP_IN") (class "Default")
      (node (ref "C33") (pin "1") (pinfunction "1_1") (pintype "passive"))
      (node (ref "RV8") (pin "P$2") (pinfunction "S_P$2") (pintype "passive"))
      (node (ref "TP6") (pin "TP") (pinfunction "TP_TP") (pintype "input"))
    )
    (net (code "8") (name "AN1") (class "Default")
      (node (ref "C14") (pin "1") (pinfunction "1_1") (pintype "passive"))
      (node (ref "R56") (pin "1") (pinfunction "1_1") (pintype "passive"))
      (node (ref "TP4") (pin "TP") (pinfunction "TP_TP") (pintype "input"))
      (node (ref "U1") (pin "7") (pinfunction "A1_7_7") (pintype "passive"))
      (node (ref "V1") (pin "1") (pinfunction "TA_1") (pintype "passive"))
      (node (ref "VR1") (pin "3") (pinfunction "A_3") (pintype "passive"))
    )
    (net (code "9") (name "AN2") (class "Default")
      (node (ref "C23") (pin "1") (pinfunction "1_1") (pintype "passive"))
      (node (ref "C24") (pin "1") (pinfunction "1_1") (pintype "passive"))
      (node (ref "R57") (pin "1") (pinfunction "1_1") (pintype "passive"))
      (node (ref "TP5") (pin "TP") (pinfunction "TP_TP") (pintype "input"))
      (node (ref "U1") (pin "10") (pinfunction "A2_10_10") (pintype "passive"))
      (node (ref "V1") (pin "6") (pinfunction "TA_6") (pintype "passive"))
      (node (ref "VR2") (pin "3") (pinfunction "A_3") (pintype "passive"))
    )
    (net (code "10") (name "BIAS") (class "Default")
      (node (ref "C13") (pin "2") (pinfunction "2_2") (pintype "passive"))
      (node (ref "C6") (pin "2") (pinfunction "2_2") (pintype "passive"))
      (node (ref "R12") (pin "1") (pinfunction "1_1") (pintype "passive"))
      (node (ref "R7") (pin "1") (pinfunction "1_1") (pintype "passive"))
      (node (ref "RV3") (pin "2") (pinfunction "S_2") (pintype "passive"))
    )
    (net (code "11") (name "FXIN") (class "Default")
      (node (ref "C3") (pin "2") (pinfunction "2_2") (pintype "passive"))
      (node (ref "Q2") (pin "2") (pinfunction "G_2") (pintype "passive"))
      (node (ref "R5") (pin "2") (pinfunction "2_2") (pintype "passive"))
      (node (ref "TP2") (pin "TP") (pinfunction "TP_TP") (pintype "input"))
    )
    (net (code "12") (name "G1") (class "Default")
      (node (ref "C5") (pin "2") (pinfunction "2_2") (pintype "passive"))
      (node (ref "R7") (pin "2") (pinfunction "2_2") (pintype "passive"))
      (node (ref "TP3") (pin "TP") (pinfunction "TP_TP") (pintype "input"))
      (node (ref "U1") (pin "4") (pinfunction "G1_4_4") (pintype "passive"))
      (node (ref "V1") (pin "2") (pinfunction "TG_2") (pintype "passive"))
    )
    (net (code "13") (name "G2") (class "Default")
      (node (ref "C22") (pin "2") (pinfunction "2_2") (pintype "passive"))
      (node (ref "R12") (pin "2") (pinfunction "2_2") (pintype "passive"))
      (node (ref "TP21") (pin "TP") (pinfunction "TP_TP") (pintype "input"))
      (node (ref "U1") (pin "14") (pinfunction "G2_14_14") (pintype "passive"))
      (node (ref "V1") (pin "7") (pinfunction "TG_7") (pintype "passive"))
    )
    (net (code "14") (name "GND") (class "Default")
      (node (ref "C1") (pin "1") (pinfunction "1_1") (pintype "passive"))
      (node (ref "C10") (pin "2") (pinfunction "2_2") (pintype "passive"))
      (node (ref "C11") (pin "1") (pinfunction "1_1") (pintype "passive"))
      (node (ref "C12") (pin "1") (pinfunction "1_1") (pintype "passive"))
      (node (ref "C13") (pin "1") (pinfunction "1_1") (pintype "passive"))
      (node (ref "C15") (pin "1") (pinfunction "1_1") (pintype "passive"))
      (node (ref "C2") (pin "2") (pinfunction "2_2") (pintype "passive"))
      (node (ref "C21") (pin "1") (pinfunction "1_1") (pintype "passive"))
      (node (ref "C25") (pin "1") (pinfunction "1_1") (pintype "passive"))
      (node (ref "C26") (pin "1") (pinfunction "1_1") (pintype "passive"))
      (node (ref "C29") (pin "1") (pinfunction "1_1") (pintype "passive"))
      (node (ref "C30") (pin "1") (pinfunction "1_1") (pintype "passive"))
      (node (ref "C31") (pin "2") (pinfunction "2_2") (pintype "passive"))
      (node (ref "C32") (pin "1") (pinfunction "1_1") (pintype "passive"))
      (node (ref "C35") (pin "2") (pinfunction "2_2") (pintype "passive"))
      (node (ref "C36") (pin "2") (pinfunction "2_2") (pintype "passive"))
      (node (ref "C37") (pin "2") (pinfunction "2_2") (pintype "passive"))
      (node (ref "C38") (pin "2") (pinfunction "2_2") (pintype "passive"))
      (node (ref "C39") (pin "2") (pinfunction "2_2") (pintype "passive"))
      (node (ref "C4") (pin "2") (pinfunction "2_2") (pintype "passive"))
      (node (ref "C40") (pin "2") (pinfunction "2_2") (pintype "passive"))
      (node (ref "C41") (pin "2") (pinfunction "2_2") (pintype "passive"))
      (node (ref "C42") (pin "2") (pinfunction "2_2") (pintype "passive"))
      (node (ref "C46") (pin "2") (pinfunction "2_2") (pintype "passive"))
      (node (ref "C47") (pin "2") (pinfunction "2_2") (pintype "passive"))
      (node (ref "C48") (pin "1") (pinfunction "1_1") (pintype "passive"))
      (node (ref "C49") (pin "2") (pinfunction "2_2") (pintype "passive"))
      (node (ref "C52") (pin "1") (pinfunction "1_1") (pintype "passive"))
      (node (ref "C53") (pin "1") (pinfunction "1_1") (pintype "passive"))
      (node (ref "C54") (pin "1") (pinfunction "1_1") (pintype "passive"))
      (node (ref "C57") (pin "2") (pinfunction "2_2") (pintype "passive"))
      (node (ref "C58") (pin "2") (pinfunction "2_2") (pintype "passive"))
      (node (ref "C59") (pin "2") (pinfunction "2_2") (pintype "passive"))
      (node (ref "C6") (pin "1") (pinfunction "1_1") (pintype "passive"))
      (node (ref "C63") (pin "2") (pinfunction "2_2") (pintype "passive"))
      (node (ref "C64") (pin "1") (pinfunction "1_1") (pintype "passive"))
      (node (ref "C65") (pin "1") (pinfunction "1_1") (pintype "passive"))
      (node (ref "C7") (pin "1") (pinfunction "1_1") (pintype "passive"))
      (node (ref "C8") (pin "1") (pinfunction "1_1") (pintype "passive"))
      (node (ref "C9") (pin "1") (pinfunction "1_1") (pintype "passive"))
      (node (ref "H2") (pin "B3,2") (pinfunction "MOUNT_B3,2") (pintype "passive"))
      (node (ref "H4") (pin "B3,2") (pinfunction "MOUNT_B3,2") (pintype "passive"))
      (node (ref "H6") (pin "B3,2") (pinfunction "MOUNT_B3,2") (pintype "passive"))
      (node (ref "H7") (pin "B3,2") (pinfunction "MOUNT_B3,2") (pintype "passive"))
      (node (ref "J1") (pin "S") (pinfunction "S_S") (pintype "passive"))
      (node (ref "J1") (pin "SN") (pinfunction "SN_SN") (pintype "passive"))
      (node (ref "J1") (pin "TN") (pinfunction "TN_TN") (pintype "passive"))
      (node (ref "J2") (pin "S") (pinfunction "S_S") (pintype "passive"))
      (node (ref "J2") (pin "SN") (pinfunction "SN_SN") (pintype "passive"))
      (node (ref "J4") (pin "1") (pinfunction "S_1") (pintype "passive"))
      (node (ref "J5") (pin "3") (pinfunction "3_3") (pintype "passive"))
      (node (ref "JP1") (pin "1") (pinfunction "1_1") (pintype "passive"))
      (node (ref "JP2") (pin "1") (pinfunction "1_1") (pintype "passive"))
      (node (ref "LSP1") (pin "MP") (pinfunction "MP_MP") (pintype "passive"))
      (node (ref "LSP2") (pin "MP") (pinfunction "MP_MP") (pintype "passive"))
      (node (ref "LSP3") (pin "MP") (pinfunction "MP_MP") (pintype "passive"))
      (node (ref "LSP4") (pin "MP") (pinfunction "MP_MP") (pintype "passive"))
      (node (ref "Q4") (pin "2") (pinfunction "G_2") (pintype "passive"))
      (node (ref "Q6") (pin "2") (pinfunction "G_2") (pintype "passive"))
      (node (ref "R14") (pin "1") (pinfunction "1_1") (pintype "passive"))
      (node (ref "R16") (pin "1") (pinfunction "1_1") (pintype "passive"))
      (node (ref "R19") (pin "1") (pinfunction "1_1") (pintype "passive"))
      (node (ref "R2") (pin "1") (pinfunction "1_1") (pintype "passive"))
      (node (ref "R21") (pin "1") (pinfunction "1_1") (pintype "passive"))
      (node (ref "R23") (pin "1") (pinfunction "1_1") (pintype "passive"))
      (node (ref "R25") (pin "1") (pinfunction "1_1") (pintype "passive"))
      (node (ref "R27") (pin "1") (pinfunction "1_1") (pintype "passive"))
      (node (ref "R29") (pin "1") (pinfunction "1_1") (pintype "passive"))
      (node (ref "R34") (pin "1") (pinfunction "1_1") (pintype "passive"))
      (node (ref "R36") (pin "1") (pinfunction "1_1") (pintype "passive"))
      (node (ref "R37") (pin "1") (pinfunction "1_1") (pintype "passive"))
      (node (ref "R4") (pin "1") (pinfunction "1_1") (pintype "passive"))
      (node (ref "R42") (pin "1") (pinfunction "1_1") (pintype "passive"))
      (node (ref "R45") (pin "1") (pinfunction "1_1") (pintype "passive"))
      (node (ref "R46") (pin "1") (pinfunction "1_1") (pintype "passive"))
      (node (ref "R48") (pin "2") (pinfunction "2_2") (pintype "passive"))
      (node (ref "R49") (pin "2") (pinfunction "2_2") (pintype "passive"))
      (node (ref "R5") (pin "1") (pinfunction "1_1") (pintype "passive"))
      (node (ref "R51") (pin "1") (pinfunction "1_1") (pintype "passive"))
      (node (ref "R54") (pin "1") (pinfunction "1_1") (pintype "passive"))
      (node (ref "R55") (pin "1") (pinfunction "1_1") (pintype "passive"))
      (node (ref "RV2") (pin "3") (pinfunction "A_3") (pintype "passive"))
      (node (ref "RV3") (pin "3") (pinfunction "A_3") (pintype "passive"))
      (node (ref "RV6") (pin "P$1") (pinfunction "A_P$1") (pintype "passive"))
      (node (ref "RV8") (pin "P$1") (pinfunction "A_P$1") (pintype "passive"))
      (node (ref "RV9") (pin "P$1") (pinfunction "A_P$1") (pintype "passive"))
      (node (ref "SW1") (pin "4") (pinfunction "G1_4") (pintype "bidirectional"))
      (node (ref "SW1") (pin "5") (pinfunction "G2_5") (pintype "bidirectional"))
      (node (ref "SW2") (pin "4") (pinfunction "G1_4") (pintype "bidirectional"))
      (node (ref "SW2") (pin "5") (pinfunction "G2_5") (pintype "bidirectional"))
      (node (ref "U1") (pin "8") (pinfunction "GND_8_8") (pintype "power_in"))
      (node (ref "U1") (pin "9") (pinfunction "F2_9_9") (pintype "passive"))
      (node (ref "U2") (pin "19") (pinfunction "PGND_2_19") (pintype "passive"))
      (node (ref "U2") (pin "24") (pinfunction "PGND_24") (pintype "passive"))
      (node (ref "U2") (pin "29") (pinfunction "EP_29") (pintype "passive"))
      (node (ref "U2") (pin "3") (pinfunction "GND_2_3") (pintype "passive"))
      (node (ref "U2") (pin "4") (pinfunction "GND_4") (pintype "passive"))
      (node (ref "U2") (pin "8") (pinfunction "AGND_8") (pintype "passive"))
      (node (ref "U3") (pin "4") (pinfunction "VCC-_4") (pintype "power_in"))
      (node (ref "U4") (pin "4") (pinfunction "GND_4") (pintype "passive"))
      (node (ref "U5") (pin "1") (pinfunction "PGND_2_1") (pintype "passive"))
      (node (ref "U5") (pin "6") (pinfunction "AGND_6") (pintype "passive"))
      (node (ref "V1") (pin "9") (pinfunction "H2_9") (pintype "passive"))
    )
    (net (code "15") (name "GVDD") (class "Default")
      (node (ref "C35") (pin "1") (pinfunction "1_1") (pintype "passive"))
      (node (ref "RV10") (pin "1") (pinfunction "E_1") (pintype "passive"))
      (node (ref "U2") (pin "9") (pinfunction "GVDD_9") (pintype "passive"))
    )
    (net (code "16") (name "HEAD_IN") (class "Default")
      (node (ref "C50") (pin "1") (pinfunction "1_1") (pintype "passive"))
      (node (ref "C51") (pin "1") (pinfunction "1_1") (pintype "passive"))
      (node (ref "TP11") (pin "TP") (pinfunction "TP_TP") (pintype "input"))
      (node (ref "U3") (pin "1") (pinfunction "OUT1_1") (pintype "output"))
      (node (ref "U3") (pin "2") (pinfunction "IN1-_2") (pintype "input"))
    )
    (net (code "17") (name "K1") (class "Default")
      (node (ref "C9") (pin "2") (pinfunction "2_2") (pintype "passive"))
      (node (ref "R8") (pin "2") (pinfunction "2_2") (pintype "passive"))
      (node (ref "U1") (pin "1") (pinfunction "F1_1_1") (pintype "passive"))
      (node (ref "U1") (pin "2") (pinfunction "F1_2_2") (pintype "passive"))
    )
    (net (code "18") (name "K2") (class "Default")
      (node (ref "C10") (pin "1") (pinfunction "1_1") (pintype "passive"))
      (node (ref "R11") (pin "2") (pinfunction "2_2") (pintype "passive"))
      (node (ref "U1") (pin "16") (pinfunction "F3_16_16") (pintype "passive"))
      (node (ref "U1") (pin "17") (pinfunction "F3_17_17") (pintype "passive"))
    )
    (net (code "19") (name "LINE_OUT") (class "Default")
      (node (ref "C45") (pin "1") (pinfunction "1_1") (pintype "passive"))
      (node (ref "TP12") (pin "TP") (pinfunction "TP_TP") (pintype "input"))
      (node (ref "U3") (pin "6") (pinfunction "IN2-_6") (pintype "input"))
      (node (ref "U3") (pin "7") (pinfunction "OUT_2_7") (pintype "output"))
    )
    (net (code "20") (name "Net-(C3-Pad1)") (class "Default")
      (node (ref "C3") (pin "1") (pinfunction "1_1") (pintype "passive"))
      (node (ref "FB1") (pin "2") (pinfunction "2_2") (pintype "passive"))
    )
    (net (code "21") (name "Net-(C16-Pad2)") (class "Default")
      (node (ref "C16") (pin "2") (pinfunction "2_2") (pintype "passive"))
      (node (ref "C17") (pin "1") (pinfunction "1_1") (pintype "passive"))
      (node (ref "R17") (pin "2") (pinfunction "2_2") (pintype "passive"))
    )
    (net (code "22") (name "Net-(C18-Pad1)") (class "Default")
      (node (ref "C18") (pin "1") (pinfunction "1_1") (pintype "passive"))
      (node (ref "C19") (pin "1") (pinfunction "1_1") (pintype "passive"))
      (node (ref "R17") (pin "1") (pinfunction "1_1") (pintype "passive"))
    )
    (net (code "23") (name "Net-(C45-Pad2)") (class "Default")
      (node (ref "C45") (pin "2") (pinfunction "2_2") (pintype "passive"))
      (node (ref "J2") (pin "T") (pinfunction "T_T") (pintype "passive"))
      (node (ref "J2") (pin "TN") (pinfunction "TN_TN") (pintype "passive"))
      (node (ref "R37") (pin "2") (pinfunction "2_2") (pintype "passive"))
      (node (ref "TP14") (pin "TP") (pinfunction "TP_TP") (pintype "input"))
    )
    (net (code "24") (name "Net-(C46-Pad1)") (class "Default")
      (node (ref "C46") (pin "1") (pinfunction "1_1") (pintype "passive"))
      (node (ref "R38") (pin "2") (pinfunction "2_2") (pintype "passive"))
    )
    (net (code "25") (name "Net-(C47-Pad1)") (class "Default")
      (node (ref "C47") (pin "1") (pinfunction "1_1") (pintype "passive"))
      (node (ref "R39") (pin "2") (pinfunction "2_2") (pintype "passive"))
    )
    (net (code "26") (name "Net-(C48-Pad2)") (class "Default")
      (node (ref "C48") (pin "2") (pinfunction "2_2") (pintype "passive"))
      (node (ref "J3") (pin "S") (pinfunction "S_S") (pintype "passive"))
      (node (ref "L1") (pin "2") (pinfunction "2_2") (pintype "passive"))
    )
    (net (code "27") (name "Net-(C49-Pad1)") (class "Default")
      (node (ref "C49") (pin "1") (pinfunction "1_1") (pintype "passive"))
      (node (ref "J3") (pin "T") (pinfunction "T_T") (pintype "passive"))
      (node (ref "L2") (pin "2") (pinfunction "2_2") (pintype "passive"))
    )
    (net (code "28") (name "Net-(C50-Pad2)") (class "Default")
      (node (ref "C50") (pin "2") (pinfunction "2_2") (pintype "passive"))
      (node (ref "R40") (pin "1") (pinfunction "1_1") (pintype "passive"))
    )
    (net (code "29") (name "Net-(C51-Pad2)") (class "Default")
      (node (ref "C51") (pin "2") (pinfunction "2_2") (pintype "passive"))
      (node (ref "R41") (pin "1") (pinfunction "1_1") (pintype "passive"))
    )
    (net (code "30") (name "Net-(FB1-Pad1)") (class "Default")
      (node (ref "FB1") (pin "1") (pinfunction "1_1") (pintype "passive"))
      (node (ref "J1") (pin "T") (pinfunction "T_T") (pintype "passive"))
    )
    (net (code "31") (name "Net-(J4-R)") (class "Default")
      (node (ref "C55") (pin "2") (pinfunction "2_2") (pintype "passive"))
      (node (ref "J4") (pin "3") (pinfunction "R_3") (pintype "passive"))
      (node (ref "TP18") (pin "TP") (pinfunction "TP_TP") (pintype "input"))
    )
    (net (code "32") (name "Net-(J4-T)") (class "Default")
      (node (ref "C56") (pin "2") (pinfunction "2_2") (pintype "passive"))
      (node (ref "J4") (pin "2") (pinfunction "T_2") (pintype "passive"))
      (node (ref "TP19") (pin "TP") (pinfunction "TP_TP") (pintype "input"))
    )
    (net (code "33") (name "Net-(LED1-C)") (class "Default")
      (node (ref "LED1") (pin "K") (pinfunction "C_K") (pintype "passive"))
      (node (ref "R45") (pin "2") (pinfunction "2_2") (pintype "passive"))
    )
    (net (code "34") (name "Net-(LED2-C)") (class "Default")
      (node (ref "LED2") (pin "K") (pinfunction "C_K") (pintype "passive"))
      (node (ref "R46") (pin "2") (pinfunction "2_2") (pintype "passive"))
    )
    (net (code "35") (name "Net-(Q2-S)") (class "Default")
      (node (ref "Q2") (pin "3") (pinfunction "S_3") (pintype "passive"))
      (node (ref "R4") (pin "2") (pinfunction "2_2") (pintype "passive"))
    )
    (net (code "36") (name "Net-(Q3-S)") (class "Default")
      (node (ref "Q3") (pin "3") (pinfunction "S_3") (pintype "passive"))
      (node (ref "R15") (pin "2") (pinfunction "2_2") (pintype "passive"))
    )
    (net (code "37") (name "Net-(Q4-S)") (class "Default")
      (node (ref "Q4") (pin "3") (pinfunction "S_3") (pintype "passive"))
      (node (ref "R16") (pin "2") (pinfunction "2_2") (pintype "passive"))
    )
    (net (code "38") (name "Net-(Q5-S)") (class "Default")
      (node (ref "Q5") (pin "3") (pinfunction "S_3") (pintype "passive"))
      (node (ref "R20") (pin "2") (pinfunction "2_2") (pintype "passive"))
    )
    (net (code "39") (name "Net-(Q6-S)") (class "Default")
      (node (ref "Q6") (pin "3") (pinfunction "S_3") (pintype "passive"))
      (node (ref "R21") (pin "2") (pinfunction "2_2") (pintype "passive"))
    )
    (net (code "40") (name "Net-(RV2-S)") (class "Default")
      (node (ref "C5") (pin "1") (pinfunction "1_1") (pintype "passive"))
      (node (ref "R53") (pin "1") (pinfunction "1_1") (pintype "passive"))
      (node (ref "RV2") (pin "2") (pinfunction "S_2") (pintype "passive"))
    )
    (net (code "41") (name "Net-(RV3-E)") (class "Default")
      (node (ref "R6") (pin "1") (pinfunction "1_1") (pintype "passive"))
      (node (ref "RV3") (pin "1") (pinfunction "E_1") (pintype "passive"))
    )
    (net (code "42") (name "Net-(RV4-A)") (class "Default")
      (node (ref "C18") (pin "2") (pinfunction "2_2") (pintype "passive"))
      (node (ref "RV4") (pin "P$1") (pinfunction "A_P$1") (pintype "passive"))
      (node (ref "RV5") (pin "P$2") (pinfunction "S_P$2") (pintype "passive"))
      (node (ref "RV5") (pin "P$3") (pinfunction "E_P$3") (pintype "passive"))
    )
    (net (code "43") (name "Net-(RV4-E)") (class "Default")
      (node (ref "C17") (pin "2") (pinfunction "2_2") (pintype "passive"))
      (node (ref "RV4") (pin "P$3") (pinfunction "E_P$3") (pintype "passive"))
    )
    (net (code "44") (name "Net-(RV4-S)") (class "Default")
      (node (ref "C20") (pin "1") (pinfunction "1_1") (pintype "passive"))
      (node (ref "RV4") (pin "P$2") (pinfunction "S_P$2") (pintype "passive"))
    )
    (net (code "45") (name "Net-(RV5-A)") (class "Default")
      (node (ref "C19") (pin "2") (pinfunction "2_2") (pintype "passive"))
      (node (ref "RV5") (pin "P$1") (pinfunction "A_P$1") (pintype "passive"))
      (node (ref "RV6") (pin "P$2") (pinfunction "S_P$2") (pintype "passive"))
      (node (ref "RV6") (pin "P$3") (pinfunction "E_P$3") (pintype "passive"))
    )
    (net (code "46") (name "Net-(RV7A-E)") (class "Default")
      (node (ref "R26") (pin "1") (pinfunction "1_1") (pintype "passive"))
      (node (ref "RV7") (pin "P$2") (pinfunction "S_P$2") (pintype "passive"))
      (node (ref "RV7") (pin "P$3") (pinfunction "E_P$3") (pintype "passive"))
    )
    (net (code "47") (name "Net-(RV7B-E)") (class "Default")
      (node (ref "R28") (pin "1") (pinfunction "1_1") (pintype "passive"))
      (node (ref "RV7") (pin "P$5") (pinfunction "S_P$5") (pintype "passive"))
      (node (ref "RV7") (pin "P$6") (pinfunction "E_P$6") (pintype "passive"))
    )
    (net (code "48") (name "Net-(RV9-S)") (class "Default")
      (node (ref "C34") (pin "1") (pinfunction "1_1") (pintype "passive"))
      (node (ref "RV9") (pin "P$2") (pinfunction "S_P$2") (pintype "passive"))
      (node (ref "TP7") (pin "TP") (pinfunction "TP_TP") (pintype "input"))
    )
    (net (code "49") (name "Net-(RV10-A)") (class "Default")
      (node (ref "R34") (pin "2") (pinfunction "2_2") (pintype "passive"))
      (node (ref "RV10") (pin "3") (pinfunction "A_3") (pintype "passive"))
    )
    (net (code "50") (name "Net-(SW3-O)") (class "Default")
      (node (ref "R49") (pin "1") (pinfunction "1_1") (pintype "passive"))
      (node (ref "SW3") (pin "1") (pinfunction "O_1") (pintype "passive"))
    )
    (net (code "51") (name "Net-(SW4-O)") (class "Default")
      (node (ref "R48") (pin "1") (pinfunction "1_1") (pintype "passive"))
      (node (ref "SW4") (pin "1") (pinfunction "O_1") (pintype "passive"))
    )
    (net (code "52") (name "Net-(U2-AVCC)") (class "Default")
      (node (ref "R52") (pin "1") (pinfunction "1_1") (pintype "passive"))
      (node (ref "U2") (pin "14") (pinfunction "AVCC_14") (pintype "power_in"))
    )
    (net (code "53") (name "Net-(U2-OUTN)") (class "Default")
      (node (ref "C44") (pin "2") (pinfunction "2_2") (pintype "passive"))
      (node (ref "L2") (pin "1") (pinfunction "1_1") (pintype "passive"))
      (node (ref "R39") (pin "1") (pinfunction "1_1") (pintype "passive"))
      (node (ref "U2") (pin "23") (pinfunction "OUTN_2_23") (pintype "passive"))
      (node (ref "U2") (pin "25") (pinfunction "OUTN_25") (pintype "output"))
    )
    (net (code "54") (name "Net-(U2-OUTP)") (class "Default")
      (node (ref "C43") (pin "1") (pinfunction "1_1") (pintype "passive"))
      (node (ref "L1") (pin "1") (pinfunction "1_1") (pintype "passive"))
      (node (ref "R38") (pin "1") (pinfunction "1_1") (pintype "passive"))
      (node (ref "U2") (pin "18") (pinfunction "OUTP_2_18") (pintype "passive"))
      (node (ref "U2") (pin "20") (pinfunction "OUTP_20") (pintype "output"))
    )
    (net (code "55") (name "Net-(U4-BYPASS)") (class "Default")
      (node (ref "C54") (pin "2") (pinfunction "2_2") (pintype "passive"))
      (node (ref "U4") (pin "3") (pinfunction "BYPASS_3") (pintype "passive"))
    )
    (net (code "56") (name "Net-(U4-IN1-)") (class "Default")
      (node (ref "R40") (pin "2") (pinfunction "2_2") (pintype "passive"))
      (node (ref "R43") (pin "1") (pinfunction "1_1") (pintype "passive"))
      (node (ref "U4") (pin "2") (pinfunction "IN1-_2") (pintype "input"))
    )
    (net (code "57") (name "Net-(U4-IN2-)") (class "Default")
      (node (ref "R41") (pin "2") (pinfunction "2_2") (pintype "passive"))
      (node (ref "R44") (pin "1") (pinfunction "1_1") (pintype "passive"))
      (node (ref "U4") (pin "6") (pinfunction "IN2-_6") (pintype "input"))
    )
    (net (code "58") (name "Net-(U4-SHDN)") (class "Default")
      (node (ref "R42") (pin "2") (pinfunction "2_2") (pintype "passive"))
      (node (ref "U4") (pin "5") (pinfunction "SHDN_5") (pintype "input"))
    )
    (net (code "59") (name "Net-(U4-VO1)") (class "Default")
      (node (ref "C55") (pin "1") (pinfunction "1_1") (pintype "passive"))
      (node (ref "R43") (pin "2") (pinfunction "2_2") (pintype "passive"))
      (node (ref "TP16") (pin "TP") (pinfunction "TP_TP") (pintype "input"))
      (node (ref "U4") (pin "1") (pinfunction "VO1_1") (pintype "output"))
    )
    (net (code "60") (name "Net-(U4-VO2)") (class "Default")
      (node (ref "C56") (pin "1") (pinfunction "1_1") (pintype "passive"))
      (node (ref "R44") (pin "2") (pinfunction "2_2") (pintype "passive"))
      (node (ref "TP17") (pin "TP") (pinfunction "TP_TP") (pintype "input"))
      (node (ref "U4") (pin "7") (pinfunction "VO2_7") (pintype "output"))
    )
    (net (code "61") (name "Net-(U5-FB)") (class "Default")
      (node (ref "R50") (pin "1") (pinfunction "1_1") (pintype "passive"))
      (node (ref "R51") (pin "2") (pinfunction "2_2") (pintype "passive"))
      (node (ref "TP20") (pin "TP") (pinfunction "TP_TP") (pintype "input"))
      (node (ref "U5") (pin "5") (pinfunction "FB_5") (pintype "passive"))
    )
    (net (code "62") (name "Net-(U5-PG)") (class "Default")
      (node (ref "R47") (pin "1") (pinfunction "1_1") (pintype "passive"))
      (node (ref "TP22") (pin "TP") (pinfunction "TP_TP") (pintype "input"))
      (node (ref "U5") (pin "7") (pinfunction "PG_7") (pintype "passive"))
    )
    (net (code "63") (name "Net-(U5-SW)") (class "Default")
      (node (ref "L4") (pin "1") (pinfunction "1_1") (pintype "passive"))
      (node (ref "U5") (pin "9") (pinfunction "SW_9") (pintype "passive"))
    )
    (net (code "64") (name "Net-(V1B-TK)") (class "Default")
      (node (ref "R55") (pin "2") (pinfunction "2_2") (pintype "passive"))
      (node (ref "V1") (pin "3") (pinfunction "TK_3") (pintype "passive"))
    )
    (net (code "65") (name "Net-(V1C-TK)") (class "Default")
      (node (ref "R54") (pin "2") (pinfunction "2_2") (pintype "passive"))
      (node (ref "V1") (pin "8") (pinfunction "TK_8") (pintype "passive"))
    )
    (net (code "66") (name "Net-(VR1-E)") (class "Default")
      (node (ref "R9") (pin "1") (pinfunction "1_1") (pintype "passive"))
      (node (ref "VR1") (pin "1") (pinfunction "E_1") (pintype "passive"))
      (node (ref "VR1") (pin "2") (pinfunction "S_2") (pintype "passive"))
    )
    (net (code "67") (name "Net-(VR2-E)") (class "Default")
      (node (ref "R10") (pin "1") (pinfunction "1_1") (pintype "passive"))
      (node (ref "VR2") (pin "1") (pinfunction "E_1") (pintype "passive"))
      (node (ref "VR2") (pin "2") (pinfunction "S_2") (pintype "passive"))
    )
    (net (code "68") (name "OUTH") (class "Default")
      (node (ref "C28") (pin "2") (pinfunction "2_2") (pintype "passive"))
      (node (ref "RV8") (pin "P$3") (pinfunction "E_P$3") (pintype "passive"))
    )
    (net (code "69") (name "OUTL") (class "Default")
      (node (ref "C27") (pin "2") (pinfunction "2_2") (pintype "passive"))
      (node (ref "RV9") (pin "P$3") (pinfunction "E_P$3") (pintype "passive"))
    )
    (net (code "70") (name "OUTL_M") (class "Default")
      (node (ref "C34") (pin "2") (pinfunction "2_2") (pintype "passive"))
      (node (ref "R35") (pin "1") (pinfunction "1_1") (pintype "passive"))
      (node (ref "R36") (pin "2") (pinfunction "2_2") (pintype "passive"))
      (node (ref "TP9") (pin "TP") (pinfunction "TP_TP") (pintype "input"))
      (node (ref "U3") (pin "3") (pinfunction "IN1+_3") (pintype "input"))
      (node (ref "U3") (pin "5") (pinfunction "IN2+_5") (pintype "input"))
    )
    (net (code "71") (name "PA_BSN") (class "Default")
      (node (ref "C44") (pin "1") (pinfunction "1_1") (pintype "passive"))
      (node (ref "U2") (pin "22") (pinfunction "BSN_2_22") (pintype "input"))
      (node (ref "U2") (pin "26") (pinfunction "BSN_26") (pintype "input"))
    )
    (net (code "72") (name "PA_BSP") (class "Default")
      (node (ref "C43") (pin "2") (pinfunction "2_2") (pintype "passive"))
      (node (ref "U2") (pin "17") (pinfunction "BSP_2_17") (pintype "input"))
      (node (ref "U2") (pin "21") (pinfunction "BSP_21") (pintype "input"))
    )
    (net (code "73") (name "PA_GAIN0") (class "Default")
      (node (ref "JP2") (pin "2") (pinfunction "2_2") (pintype "passive"))
      (node (ref "R32") (pin "1") (pinfunction "1_1") (pintype "passive"))
      (node (ref "U2") (pin "5") (pinfunction "GAIN0_5") (pintype "input"))
    )
    (net (code "74") (name "PA_GAIN1") (class "Default")
      (node (ref "JP1") (pin "2") (pinfunction "2_2") (pintype "passive"))
      (node (ref "R31") (pin "1") (pinfunction "1_1") (pintype "passive"))
      (node (ref "U2") (pin "6") (pinfunction "GAIN1_6") (pintype "input"))
    )
    (net (code "75") (name "PA_INN") (class "Default")
      (node (ref "C32") (pin "2") (pinfunction "2_2") (pintype "passive"))
      (node (ref "U2") (pin "11") (pinfunction "INN_11") (pintype "input"))
    )
    (net (code "76") (name "PA_INP") (class "Default")
      (node (ref "C33") (pin "2") (pinfunction "2_2") (pintype "passive"))
      (node (ref "U2") (pin "12") (pinfunction "INP_12") (pintype "input"))
    )
    (net (code "77") (name "PA_SD_N") (class "Default")
      (node (ref "R30") (pin "1") (pinfunction "1_1") (pintype "passive"))
      (node (ref "TP13") (pin "TP") (pinfunction "TP_TP") (pintype "input"))
      (node (ref "U2") (pin "1") (pinfunction "~{SD}_1") (pintype "input"))
      (node (ref "U2") (pin "2") (pinfunction "~{FAULT}_2") (pintype "output"))
    )
    (net (code "78") (name "Q1D") (class "Default")
      (node (ref "Q1") (pin "1") (pinfunction "D_1") (pintype "passive"))
      (node (ref "R53") (pin "2") (pinfunction "2_2") (pintype "passive"))
      (node (ref "RV1") (pin "P$1") (pinfunction "A_P$1") (pintype "passive"))
      (node (ref "RV2") (pin "1") (pinfunction "E_1") (pintype "passive"))
      (node (ref "TP1") (pin "TP") (pinfunction "TP_TP") (pintype "input"))
    )
    (net (code "79") (name "Q1D2") (class "Default")
      (node (ref "R3") (pin "1") (pinfunction "1_1") (pintype "passive"))
      (node (ref "RV1") (pin "P$2") (pinfunction "S_P$2") (pintype "passive"))
      (node (ref "RV1") (pin "P$3") (pinfunction "E_P$3") (pintype "passive"))
    )
    (net (code "80") (name "Q1G") (class "Default")
      (node (ref "Q1") (pin "2") (pinfunction "G_2") (pintype "passive"))
      (node (ref "R1") (pin "1") (pinfunction "1_1") (pintype "passive"))
      (node (ref "R2") (pin "2") (pinfunction "2_2") (pintype "passive"))
    )
    (net (code "81") (name "Q2D") (class "Default")
      (node (ref "Q1") (pin "3") (pinfunction "S_3") (pintype "passive"))
      (node (ref "Q2") (pin "1") (pinfunction "D_1") (pintype "passive"))
    )
    (net (code "82") (name "Q3G") (class "Default")
      (node (ref "C14") (pin "2") (pinfunction "2_2") (pintype "passive"))
      (node (ref "Q3") (pin "2") (pinfunction "G_2") (pintype "passive"))
      (node (ref "R13") (pin "1") (pinfunction "1_1") (pintype "passive"))
      (node (ref "R14") (pin "2") (pinfunction "2_2") (pintype "passive"))
    )
    (net (code "83") (name "Q3SC") (class "Default")
      (node (ref "C29") (pin "2") (pinfunction "2_2") (pintype "passive"))
      (node (ref "SW2") (pin "2") (pinfunction "P_2") (pintype "passive"))
    )
    (net (code "84") (name "Q4D") (class "Default")
      (node (ref "C16") (pin "1") (pinfunction "1_1") (pintype "passive"))
      (node (ref "Q4") (pin "1") (pinfunction "D_1") (pintype "passive"))
      (node (ref "R15") (pin "1") (pinfunction "1_1") (pintype "passive"))
    )
    (net (code "85") (name "Q5G") (class "Default")
      (node (ref "C20") (pin "2") (pinfunction "2_2") (pintype "passive"))
      (node (ref "Q5") (pin "2") (pinfunction "G_2") (pintype "passive"))
      (node (ref "R18") (pin "1") (pinfunction "1_1") (pintype "passive"))
      (node (ref "R19") (pin "2") (pinfunction "2_2") (pintype "passive"))
    )
    (net (code "86") (name "Q6D") (class "Default")
      (node (ref "C22") (pin "1") (pinfunction "1_1") (pintype "passive"))
      (node (ref "Q6") (pin "1") (pinfunction "D_1") (pintype "passive"))
      (node (ref "R20") (pin "1") (pinfunction "1_1") (pintype "passive"))
    )
    (net (code "87") (name "Q7D") (class "Default")
      (node (ref "C28") (pin "1") (pinfunction "1_1") (pintype "passive"))
      (node (ref "Q7") (pin "1") (pinfunction "D_1") (pintype "passive"))
      (node (ref "RV7") (pin "P$1") (pinfunction "A_P$1") (pintype "passive"))
    )
    (net (code "88") (name "Q7G") (class "Default")
      (node (ref "Q7") (pin "2") (pinfunction "G_2") (pintype "passive"))
      (node (ref "R22") (pin "1") (pinfunction "1_1") (pintype "passive"))
      (node (ref "R23") (pin "2") (pinfunction "2_2") (pintype "passive"))
    )
    (net (code "89") (name "Q8D") (class "Default")
      (node (ref "Q7") (pin "3") (pinfunction "S_3") (pintype "passive"))
      (node (ref "Q8") (pin "1") (pinfunction "D_1") (pintype "passive"))
    )
    (net (code "90") (name "Q8G") (class "Default")
      (node (ref "C24") (pin "2") (pinfunction "2_2") (pintype "passive"))
      (node (ref "Q8") (pin "2") (pinfunction "G_2") (pintype "passive"))
    )
    (net (code "91") (name "Q8S") (class "Default")
      (node (ref "Q8") (pin "3") (pinfunction "S_3") (pintype "passive"))
      (node (ref "R27") (pin "2") (pinfunction "2_2") (pintype "passive"))
      (node (ref "SW2") (pin "1") (pinfunction "O_1") (pintype "passive"))
    )
    (net (code "92") (name "Q9D") (class "Default")
      (node (ref "C27") (pin "1") (pinfunction "1_1") (pintype "passive"))
      (node (ref "Q9") (pin "1") (pinfunction "D_1") (pintype "passive"))
      (node (ref "RV7") (pin "P$4") (pinfunction "A_P$4") (pintype "passive"))
    )
    (net (code "93") (name "Q9G") (class "Default")
      (node (ref "Q9") (pin "2") (pinfunction "G_2") (pintype "passive"))
      (node (ref "R24") (pin "1") (pinfunction "1_1") (pintype "passive"))
      (node (ref "R25") (pin "2") (pinfunction "2_2") (pintype "passive"))
    )
    (net (code "94") (name "Q10D") (class "Default")
      (node (ref "Q10") (pin "1") (pinfunction "D_1") (pintype "passive"))
      (node (ref "Q9") (pin "3") (pinfunction "S_3") (pintype "passive"))
    )
    (net (code "95") (name "Q10G") (class "Default")
      (node (ref "C23") (pin "2") (pinfunction "2_2") (pintype "passive"))
      (node (ref "Q10") (pin "2") (pinfunction "G_2") (pintype "passive"))
    )
    (net (code "96") (name "Q10S") (class "Default")
      (node (ref "Q10") (pin "3") (pinfunction "S_3") (pintype "passive"))
      (node (ref "R29") (pin "2") (pinfunction "2_2") (pintype "passive"))
      (node (ref "SW1") (pin "1") (pinfunction "O_1") (pintype "passive"))
    )
    (net (code "97") (name "Q10SC") (class "Default")
      (node (ref "C30") (pin "2") (pinfunction "2_2") (pintype "passive"))
      (node (ref "SW1") (pin "2") (pinfunction "P_2") (pintype "passive"))
    )
    (net (code "98") (name "VCC") (class "Default")
      (node (ref "C31") (pin "1") (pinfunction "1_1") (pintype "passive"))
      (node (ref "R33") (pin "2") (pinfunction "2_2") (pintype "passive"))
      (node (ref "R52") (pin "2") (pinfunction "2_2") (pintype "passive"))
      (node (ref "TP8") (pin "TP") (pinfunction "TP_TP") (pintype "input"))
      (node (ref "U2") (pin "7") (pinfunction "AVCC_2_7") (pintype "power_in"))
    )
    (net (code "99") (name "unconnected-(J3-PadSN)") (class "Default")
      (node (ref "J3") (pin "SN") (pinfunction "SN_SN") (pintype "passive"))
    )
    (net (code "100") (name "unconnected-(J3-PadTN)") (class "Default")
      (node (ref "J3") (pin "TN") (pinfunction "TN_TN") (pintype "passive"))
    )
    (net (code "101") (name "unconnected-(J4-RN-Pad11)") (class "Default")
      (node (ref "J4") (pin "11") (pinfunction "RN_11") (pintype "passive"))
    )
    (net (code "102") (name "unconnected-(J4-TN-Pad10)") (class "Default")
      (node (ref "J4") (pin "10") (pinfunction "TN_10") (pintype "passive"))
    )
    (net (code "103") (name "unconnected-(J5-Pad2)") (class "Default")
      (node (ref "J5") (pin "2") (pinfunction "2_2") (pintype "passive"))
    )
    (net (code "104") (name "unconnected-(SW1-S-Pad3)") (class "Default")
      (node (ref "SW1") (pin "3") (pinfunction "S_3") (pintype "passive"))
    )
    (net (code "105") (name "unconnected-(SW2-S-Pad3)") (class "Default")
      (node (ref "SW2") (pin "3") (pinfunction "S_3") (pintype "passive"))
    )
    (net (code "106") (name "unconnected-(U2-NC-Pad13)") (class "Default")
      (node (ref "U2") (pin "13") (pinfunction "NC_13") (pintype "no_connect"))
    )
    (net (code "107") (name "unconnected-(U5-NC-Pad4)") (class "Default")
      (node (ref "U5") (pin "4") (pinfunction "NC_4") (pintype "passive"))
    )
  )
)
